# pathfinder_sch.net
KiCad netlist of a schematic drawn in Altium Designer
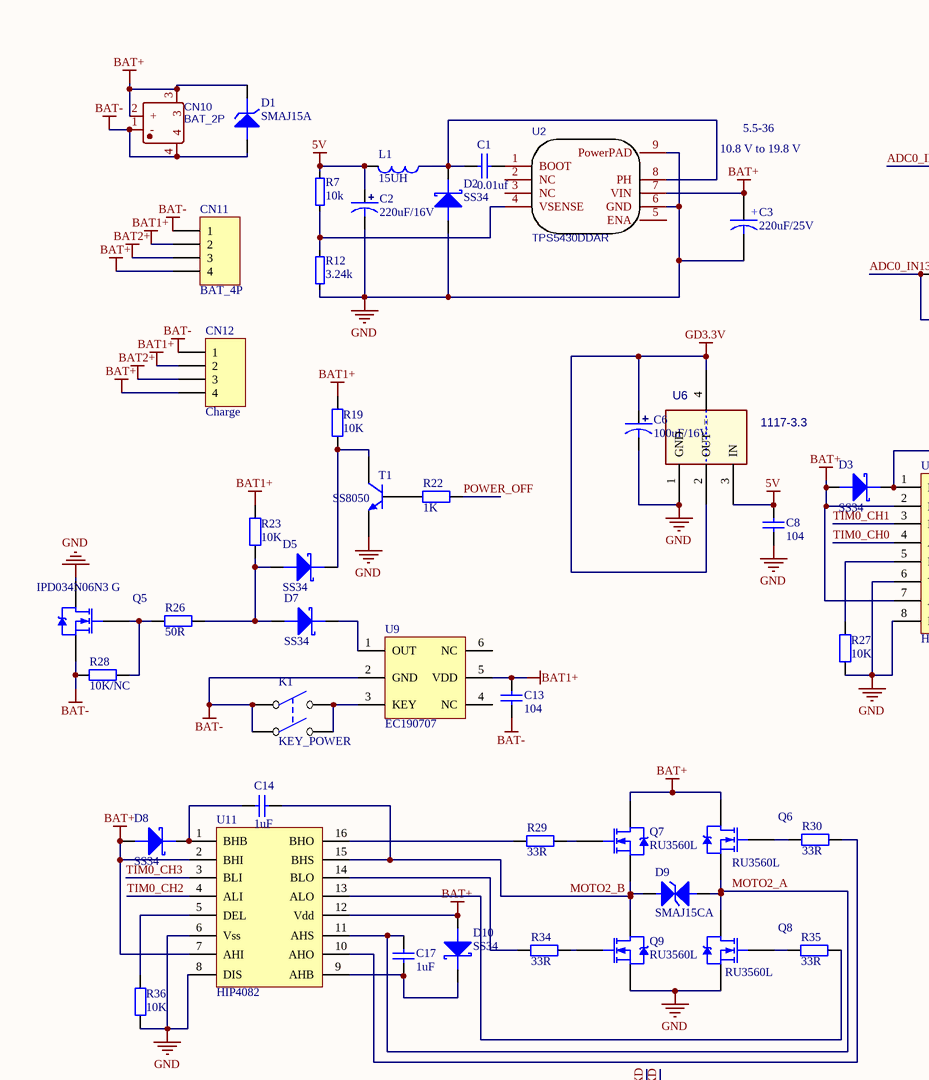
[diagram p0: pathfinder_sch.SchDoc, top left]
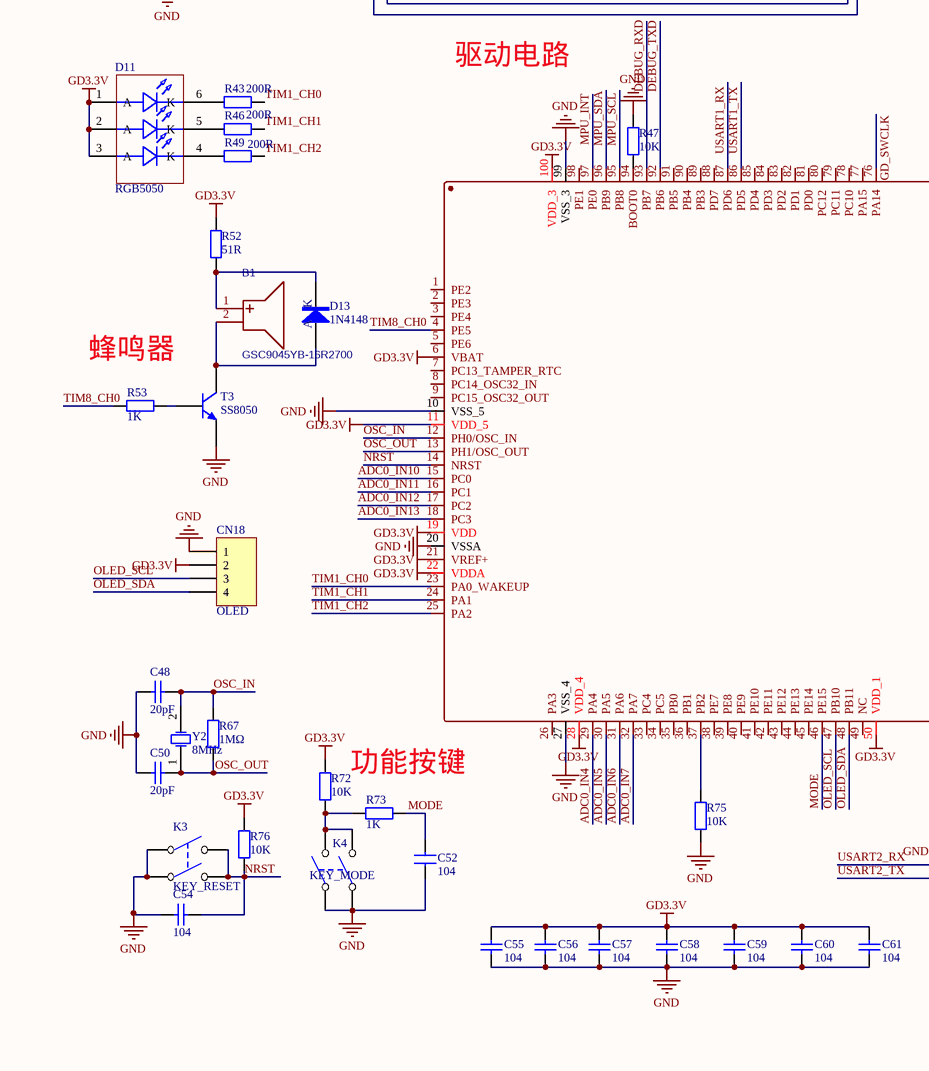
[diagram p1: pathfinder_sch.SchDoc, bottom left]
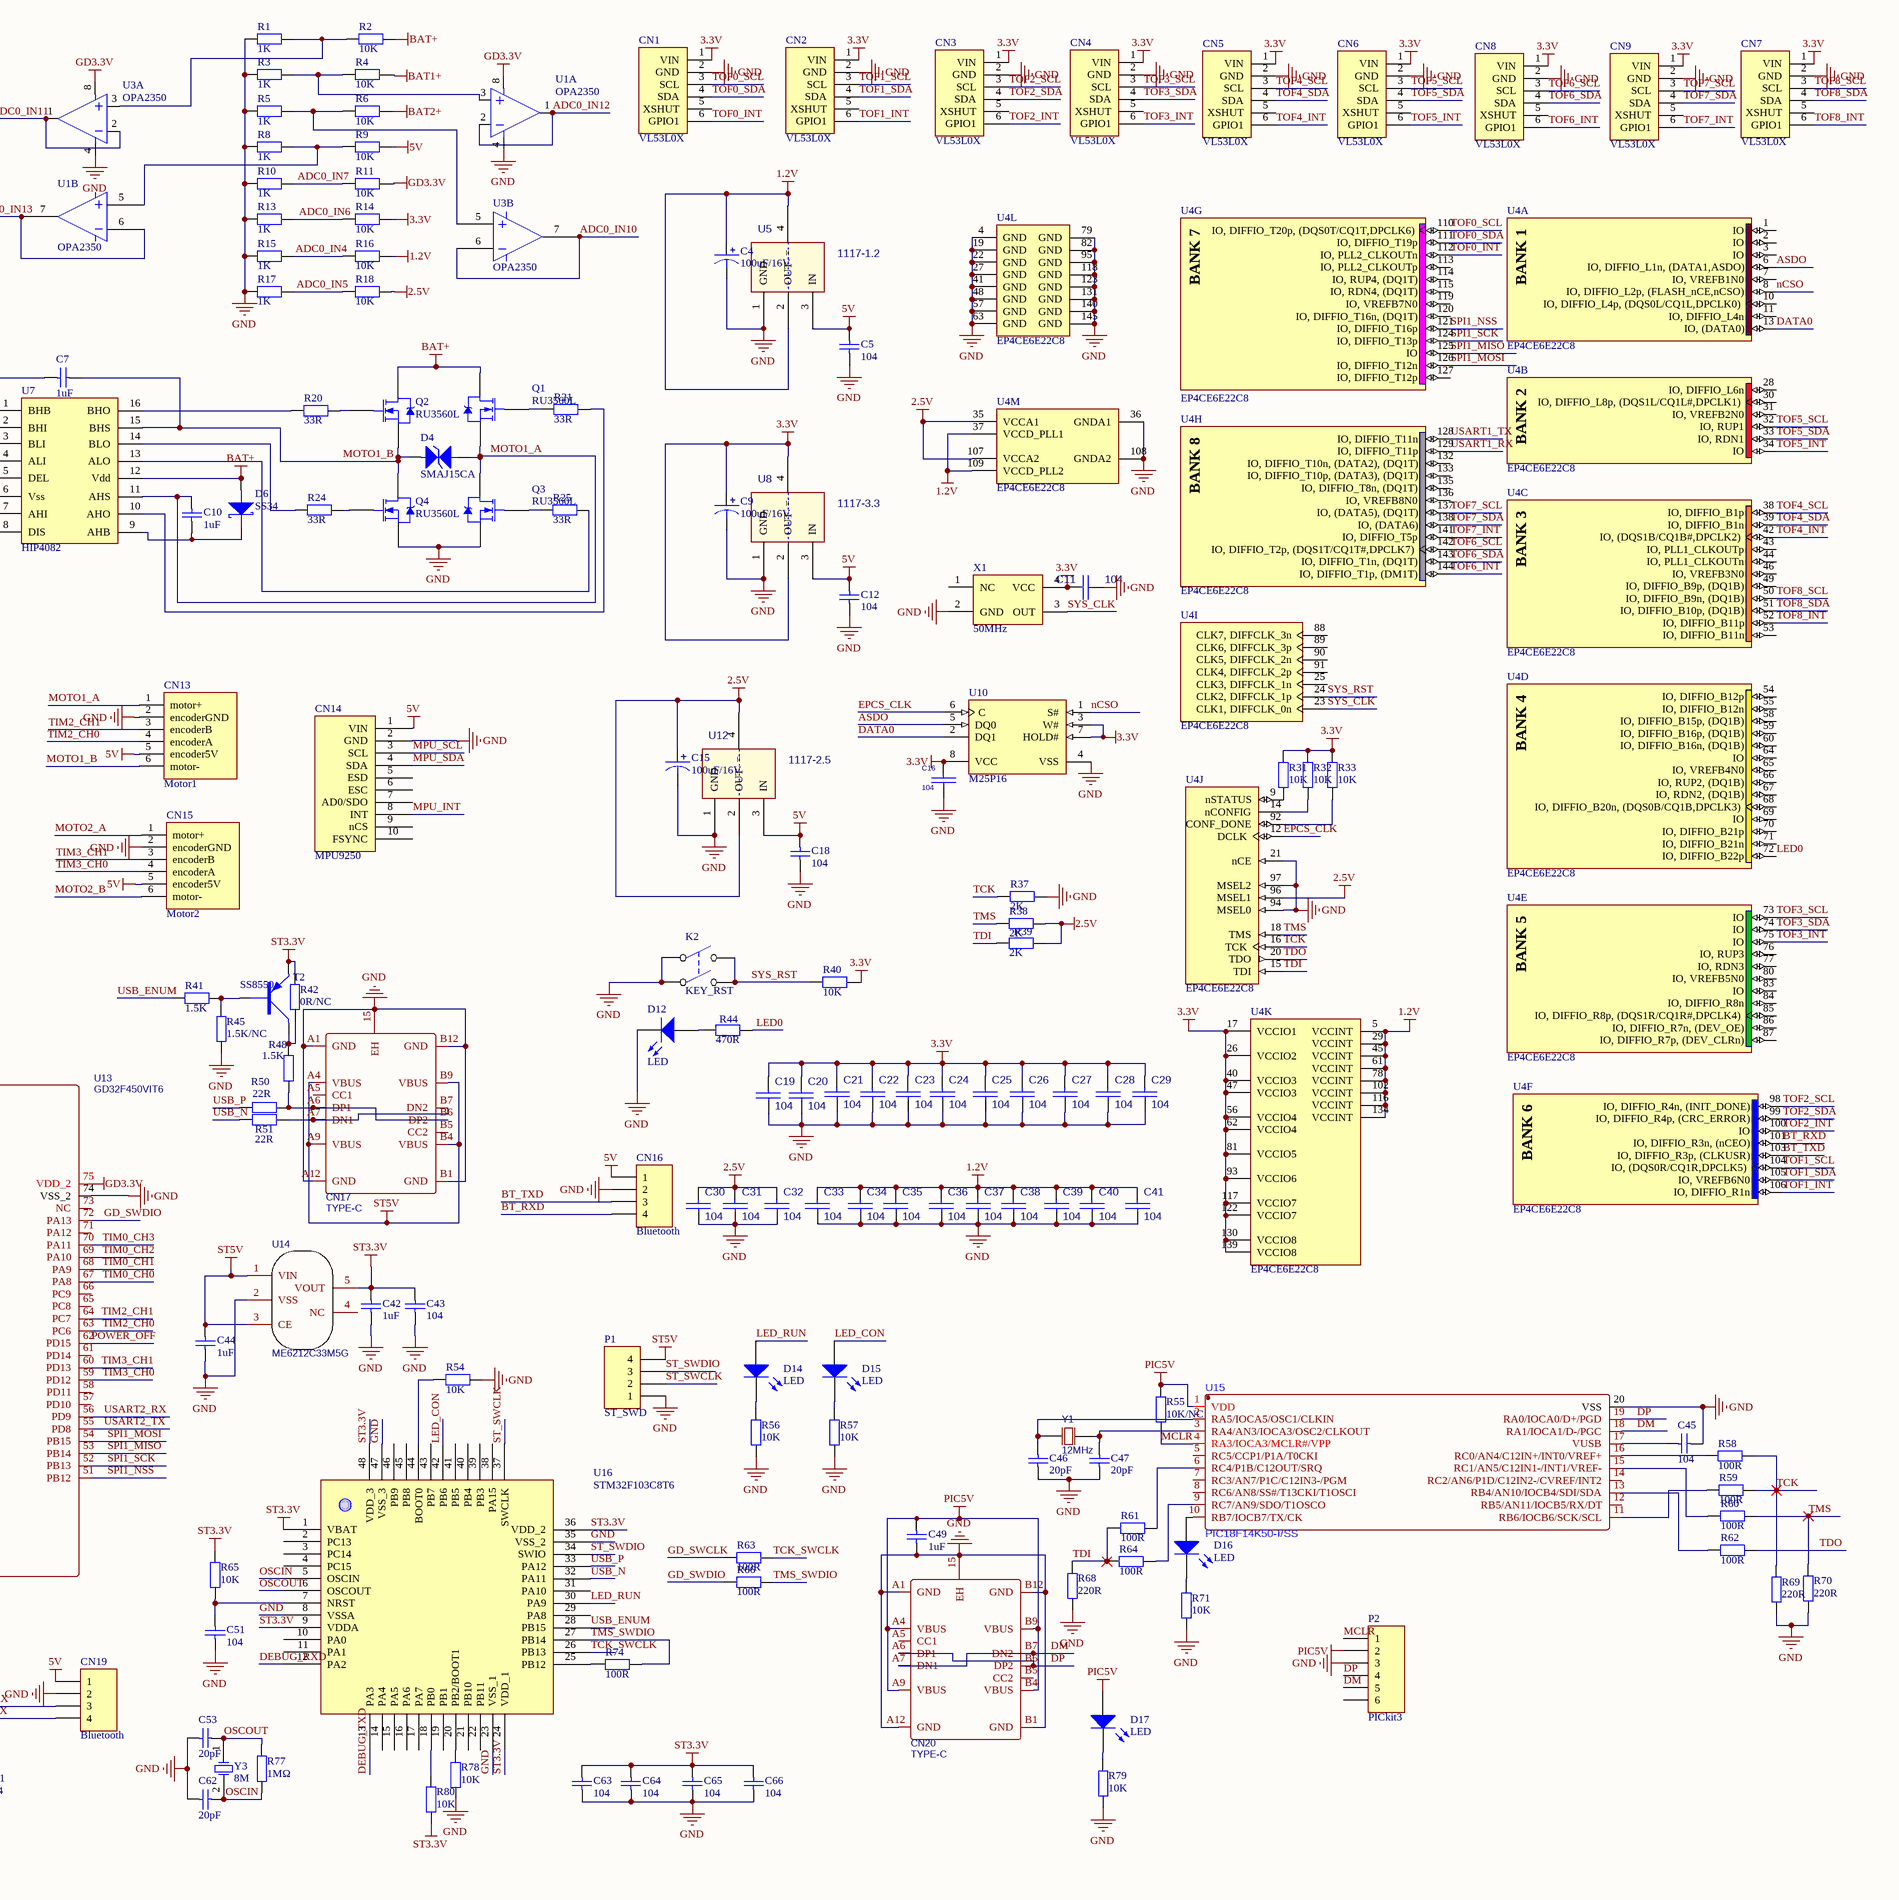
[diagram p2: pathfinder_sch.SchDoc, bottom right]

(export (version "E")
  (design (tool "Eeschema 10.0.6"))
  (components
    (comp (ref "B1")
      (value "GSC9045YB-16R2700")
      (footprint "BUZ-SMD_GSC9045YB-16R2700")
      (description "无源蜂鸣器")
      (fields (field (name "BOM_SUPPLIER PART") "C255324") (field (name "CONTRIBUTOR") "LCSC"))
      (libsource (lib "1") (part "GSC9045YB-16R2700"))
    )
    (comp (ref "C1")
      (value "0.01uf")
      (footprint "0603-JLC")
      (description "C0603")
      (libsource (lib "电容") (part "普通电容"))
    )
    (comp (ref "C2")
      (value "220uF/16V")
      (footprint "SMD,6.3x5.3mm")
      (description "6.3*5.3mm铝电解电容")
      (libsource (lib "电容") (part "SMD_ECAP"))
    )
    (comp (ref "C3")
      (value "220uF/25V")
      (footprint "SMD,6.3x5.8mm")
      (description "贴片铝电解电容SMD,6.3x5.8mm")
      (libsource (lib "*") (part "CAP极性"))
    )
    (comp (ref "C4")
      (value "100uF/16V")
      (footprint "SMD,6.3x5.3mm")
      (description "6.3*5.3mm铝电解电容")
      (libsource (lib "电容") (part "SMD_ECAP"))
    )
    (comp (ref "C5")
      (value "104")
      (footprint "0603-JLC")
      (description "C0603")
      (fields (field (name "PUBLISHER") "Altium Limited"))
      (libsource (lib "Miscellaneous Devices") (part "Cap"))
    )
    (comp (ref "C6")
      (value "100uF/16V")
      (footprint "SMD,6.3x5.3mm")
      (description "6.3*5.3mm铝电解电容")
      (libsource (lib "电容") (part "SMD_ECAP"))
    )
    (comp (ref "C7")
      (value "1uF")
      (footprint "0603-JLC")
      (description "C0603")
      (fields (field (name "PUBLISHER") "Altium Limited"))
      (libsource (lib "Miscellaneous Devices") (part "Cap"))
    )
    (comp (ref "C8")
      (value "104")
      (footprint "0603-JLC")
      (description "C0603")
      (fields (field (name "PUBLISHER") "Altium Limited"))
      (libsource (lib "Miscellaneous Devices") (part "Cap"))
    )
    (comp (ref "C9")
      (value "100uF/16V")
      (footprint "SMD,6.3x5.3mm")
      (description "6.3*5.3mm铝电解电容")
      (libsource (lib "电容") (part "SMD_ECAP"))
    )
    (comp (ref "C10")
      (value "1uF")
      (footprint "0603-JLC")
      (description "C0603")
      (fields (field (name "PUBLISHER") "Altium Limited"))
      (libsource (lib "Miscellaneous Devices") (part "Cap"))
    )
    (comp (ref "C11")
      (value "104")
      (footprint "0603-JLC")
      (description "C0603")
      (libsource (lib "Miscellaneous Devices") (part "C_Dup3"))
    )
    (comp (ref "C12")
      (value "104")
      (footprint "0603-JLC")
      (description "C0603")
      (fields (field (name "PUBLISHER") "Altium Limited"))
      (libsource (lib "Miscellaneous Devices") (part "Cap"))
    )
    (comp (ref "C13")
      (value "104")
      (footprint "0603-JLC")
      (description "C0603")
      (fields (field (name "PUBLISHER") "Altium Limited"))
      (libsource (lib "Miscellaneous Devices") (part "Cap"))
    )
    (comp (ref "C14")
      (value "1uF")
      (footprint "0603-JLC")
      (description "C0603")
      (fields (field (name "PUBLISHER") "Altium Limited"))
      (libsource (lib "Miscellaneous Devices") (part "Cap"))
    )
    (comp (ref "C15")
      (value "100uF/16V")
      (footprint "SMD,6.3x5.3mm")
      (description "6.3*5.3mm铝电解电容")
      (libsource (lib "电容") (part "SMD_ECAP"))
    )
    (comp (ref "C16")
      (value "104")
      (footprint "0603-JLC")
      (description "C0603")
      (libsource (lib "Miscellaneous Devices") (part "C"))
    )
    (comp (ref "C17")
      (value "1uF")
      (footprint "0603-JLC")
      (description "C0603")
      (fields (field (name "PUBLISHER") "Altium Limited"))
      (libsource (lib "Miscellaneous Devices") (part "Cap"))
    )
    (comp (ref "C18")
      (value "104")
      (footprint "0603-JLC")
      (description "C0603")
      (fields (field (name "PUBLISHER") "Altium Limited"))
      (libsource (lib "Miscellaneous Devices") (part "Cap"))
    )
    (comp (ref "C19")
      (value "104")
      (footprint "0603-JLC")
      (description "C0603")
      (libsource (lib "Miscellaneous Devices") (part "C_Dup4"))
    )
    (comp (ref "C20")
      (value "104")
      (footprint "0603-JLC")
      (description "C0603")
      (libsource (lib "Miscellaneous Devices") (part "C_Dup4"))
    )
    (comp (ref "C21")
      (value "104")
      (footprint "0603-JLC")
      (description "C0603")
      (libsource (lib "Miscellaneous Devices") (part "C_Dup4"))
    )
    (comp (ref "C22")
      (value "104")
      (footprint "0603-JLC")
      (description "C0603")
      (libsource (lib "Miscellaneous Devices") (part "C_Dup4"))
    )
    (comp (ref "C23")
      (value "104")
      (footprint "0603-JLC")
      (description "C0603")
      (libsource (lib "Miscellaneous Devices") (part "C_Dup4"))
    )
    (comp (ref "C24")
      (value "104")
      (footprint "0603-JLC")
      (description "C0603")
      (libsource (lib "Miscellaneous Devices") (part "C_Dup4"))
    )
    (comp (ref "C25")
      (value "104")
      (footprint "0603-JLC")
      (description "C0603")
      (libsource (lib "Miscellaneous Devices") (part "C_Dup4"))
    )
    (comp (ref "C26")
      (value "104")
      (footprint "0603-JLC")
      (description "C0603")
      (libsource (lib "Miscellaneous Devices") (part "C_Dup4"))
    )
    (comp (ref "C27")
      (value "104")
      (footprint "0603-JLC")
      (description "C0603")
      (libsource (lib "Miscellaneous Devices") (part "C_Dup4"))
    )
    (comp (ref "C28")
      (value "104")
      (footprint "0603-JLC")
      (description "C0603")
      (libsource (lib "Miscellaneous Devices") (part "C_Dup4"))
    )
    (comp (ref "C29")
      (value "104")
      (footprint "0603-JLC")
      (description "C0603")
      (libsource (lib "Miscellaneous Devices") (part "C_Dup4"))
    )
    (comp (ref "C30")
      (value "104")
      (footprint "0603-JLC")
      (description "C0603")
      (libsource (lib "Miscellaneous Devices") (part "C_Dup4"))
    )
    (comp (ref "C31")
      (value "104")
      (footprint "0603-JLC")
      (description "C0603")
      (libsource (lib "Miscellaneous Devices") (part "C_Dup4"))
    )
    (comp (ref "C32")
      (value "104")
      (footprint "0603-JLC")
      (description "C0603")
      (libsource (lib "Miscellaneous Devices") (part "C_Dup4"))
    )
    (comp (ref "C33")
      (value "104")
      (footprint "0603-JLC")
      (description "C0603")
      (libsource (lib "Miscellaneous Devices") (part "C_Dup4"))
    )
    (comp (ref "C34")
      (value "104")
      (footprint "0603-JLC")
      (description "C0603")
      (libsource (lib "Miscellaneous Devices") (part "C_Dup4"))
    )
    (comp (ref "C35")
      (value "104")
      (footprint "0603-JLC")
      (description "C0603")
      (libsource (lib "Miscellaneous Devices") (part "C_Dup4"))
    )
    (comp (ref "C36")
      (value "104")
      (footprint "0603-JLC")
      (description "C0603")
      (libsource (lib "Miscellaneous Devices") (part "C_Dup4"))
    )
    (comp (ref "C37")
      (value "104")
      (footprint "0603-JLC")
      (description "C0603")
      (libsource (lib "Miscellaneous Devices") (part "C_Dup4"))
    )
    (comp (ref "C38")
      (value "104")
      (footprint "0603-JLC")
      (description "C0603")
      (libsource (lib "Miscellaneous Devices") (part "C_Dup4"))
    )
    (comp (ref "C39")
      (value "104")
      (footprint "0603-JLC")
      (description "C0603")
      (libsource (lib "Miscellaneous Devices") (part "C_Dup4"))
    )
    (comp (ref "C40")
      (value "104")
      (footprint "0603-JLC")
      (description "C0603")
      (libsource (lib "Miscellaneous Devices") (part "C_Dup4"))
    )
    (comp (ref "C41")
      (value "104")
      (footprint "0603-JLC")
      (description "C0603")
      (libsource (lib "Miscellaneous Devices") (part "C_Dup4"))
    )
    (comp (ref "C42")
      (value "1uF")
      (footprint "0603-JLC")
      (description "C0603")
      (fields (field (name "PUBLISHER") "Altium Limited"))
      (libsource (lib "Miscellaneous Devices") (part "Cap"))
    )
    (comp (ref "C43")
      (value "104")
      (footprint "0603-JLC")
      (description "C0603")
      (fields (field (name "PUBLISHER") "Altium Limited"))
      (libsource (lib "Miscellaneous Devices") (part "Cap"))
    )
    (comp (ref "C44")
      (value "1uF")
      (footprint "0603-JLC")
      (description "C0603")
      (fields (field (name "PUBLISHER") "Altium Limited"))
      (libsource (lib "Miscellaneous Devices") (part "Cap"))
    )
    (comp (ref "C45")
      (value "104")
      (footprint "0603-JLC")
      (description "C0603")
      (fields (field (name "PUBLISHER") "Altium Limited"))
      (libsource (lib "Miscellaneous Devices") (part "Cap"))
    )
    (comp (ref "C46")
      (value "20pF")
      (footprint "0603-JLC")
      (description "C0603")
      (fields (field (name "PUBLISHER") "Altium Limited"))
      (libsource (lib "STM32F103C8T6") (part "Cap"))
    )
    (comp (ref "C47")
      (value "20pF")
      (footprint "0603-JLC")
      (description "C0603")
      (fields (field (name "PUBLISHER") "Altium Limited"))
      (libsource (lib "STM32F103C8T6") (part "Cap"))
    )
    (comp (ref "C48")
      (value "20pF")
      (footprint "0603-JLC")
      (description "C0603")
      (fields (field (name "PUBLISHER") "Altium Limited"))
      (libsource (lib "Miscellaneous Devices") (part "Cap"))
    )
    (comp (ref "C49")
      (value "1uF")
      (footprint "0603-JLC")
      (description "C0603")
      (fields (field (name "PUBLISHER") "Altium Limited"))
      (libsource (lib "Miscellaneous Devices") (part "Cap"))
    )
    (comp (ref "C50")
      (value "20pF")
      (footprint "0603-JLC")
      (description "C0603")
      (fields (field (name "PUBLISHER") "Altium Limited"))
      (libsource (lib "Miscellaneous Devices") (part "Cap"))
    )
    (comp (ref "C51")
      (value "104")
      (footprint "0603-JLC")
      (description "C0603")
      (fields (field (name "PUBLISHER") "Altium Limited"))
      (libsource (lib "Miscellaneous Devices") (part "Cap"))
    )
    (comp (ref "C52")
      (value "104")
      (footprint "0603-JLC")
      (description "C0603")
      (libsource (lib "*") (part "CAP"))
    )
    (comp (ref "C53")
      (value "20pF")
      (footprint "0603-JLC")
      (description "C0603")
      (fields (field (name "PUBLISHER") "Altium Limited"))
      (libsource (lib "STM32F103C8T6") (part "Cap"))
    )
    (comp (ref "C54")
      (value "104")
      (footprint "0603-JLC")
      (description "C0603")
      (fields (field (name "PUBLISHER") "Altium Limited"))
      (libsource (lib "Miscellaneous Devices") (part "Cap"))
    )
    (comp (ref "C55")
      (value "104")
      (footprint "0603-JLC")
      (description "C0603")
      (fields (field (name "PUBLISHER") "Altium Limited"))
      (libsource (lib "Miscellaneous Devices") (part "Cap"))
    )
    (comp (ref "C56")
      (value "104")
      (footprint "0603-JLC")
      (description "C0603")
      (fields (field (name "PUBLISHER") "Altium Limited"))
      (libsource (lib "Miscellaneous Devices") (part "Cap"))
    )
    (comp (ref "C57")
      (value "104")
      (footprint "0603-JLC")
      (description "C0603")
      (fields (field (name "PUBLISHER") "Altium Limited"))
      (libsource (lib "Miscellaneous Devices") (part "Cap"))
    )
    (comp (ref "C58")
      (value "104")
      (footprint "0603-JLC")
      (description "C0603")
      (fields (field (name "PUBLISHER") "Altium Limited"))
      (libsource (lib "Miscellaneous Devices") (part "Cap"))
    )
    (comp (ref "C59")
      (value "104")
      (footprint "0603-JLC")
      (description "C0603")
      (fields (field (name "PUBLISHER") "Altium Limited"))
      (libsource (lib "Miscellaneous Devices") (part "Cap"))
    )
    (comp (ref "C60")
      (value "104")
      (footprint "0603-JLC")
      (description "C0603")
      (fields (field (name "PUBLISHER") "Altium Limited"))
      (libsource (lib "Miscellaneous Devices") (part "Cap"))
    )
    (comp (ref "C61")
      (value "104")
      (footprint "0603-JLC")
      (description "C0603")
      (fields (field (name "PUBLISHER") "Altium Limited"))
      (libsource (lib "Miscellaneous Devices") (part "Cap"))
    )
    (comp (ref "C62")
      (value "20pF")
      (footprint "0603-JLC")
      (description "C0603")
      (fields (field (name "PUBLISHER") "Altium Limited"))
      (libsource (lib "STM32F103C8T6") (part "Cap"))
    )
    (comp (ref "C63")
      (value "104")
      (footprint "0603-JLC")
      (description "C0603")
      (fields (field (name "PUBLISHER") "Altium Limited"))
      (libsource (lib "Miscellaneous Devices") (part "Cap"))
    )
    (comp (ref "C64")
      (value "104")
      (footprint "0603-JLC")
      (description "C0603")
      (fields (field (name "PUBLISHER") "Altium Limited"))
      (libsource (lib "Miscellaneous Devices") (part "Cap"))
    )
    (comp (ref "C65")
      (value "104")
      (footprint "0603-JLC")
      (description "C0603")
      (fields (field (name "PUBLISHER") "Altium Limited"))
      (libsource (lib "Miscellaneous Devices") (part "Cap"))
    )
    (comp (ref "C66")
      (value "104")
      (footprint "0603-JLC")
      (description "C0603")
      (fields (field (name "PUBLISHER") "Altium Limited"))
      (libsource (lib "Miscellaneous Devices") (part "Cap"))
    )
    (comp (ref "CN1")
      (value "VL53L0X")
      (footprint "HDR1X6")
      (description "弯针单排母座2.54mm 6P")
      (libsource (lib "Schlib1") (part "VL53L0X"))
    )
    (comp (ref "CN2")
      (value "VL53L0X")
      (footprint "HDR1X6")
      (description "弯针单排母座2.54mm 6P")
      (libsource (lib "Schlib1") (part "VL53L0X"))
    )
    (comp (ref "CN3")
      (value "VL53L0X")
      (footprint "HDR1X6")
      (description "弯针单排母座2.54mm 6P")
      (libsource (lib "Schlib1") (part "VL53L0X"))
    )
    (comp (ref "CN4")
      (value "VL53L0X")
      (footprint "HDR1X6")
      (description "弯针单排母座2.54mm 6P")
      (libsource (lib "Schlib1") (part "VL53L0X"))
    )
    (comp (ref "CN5")
      (value "VL53L0X")
      (footprint "HDR1X6")
      (description "弯针单排母座2.54mm 6P")
      (libsource (lib "Schlib1") (part "VL53L0X"))
    )
    (comp (ref "CN6")
      (value "VL53L0X")
      (footprint "HDR1X6")
      (description "弯针单排母座2.54mm 6P")
      (libsource (lib "Schlib1") (part "VL53L0X"))
    )
    (comp (ref "CN7")
      (value "VL53L0X")
      (footprint "HDR1X6")
      (description "弯针单排母座2.54mm 6P")
      (libsource (lib "Schlib1") (part "VL53L0X"))
    )
    (comp (ref "CN8")
      (value "VL53L0X")
      (footprint "HDR1X6")
      (description "弯针单排母座2.54mm 6P")
      (libsource (lib "Schlib1") (part "VL53L0X"))
    )
    (comp (ref "CN9")
      (value "VL53L0X")
      (footprint "HDR1X6")
      (description "弯针单排母座2.54mm 6P")
      (libsource (lib "Schlib1") (part "VL53L0X"))
    )
    (comp (ref "CN10")
      (value "BAT_2P")
      (footprint "CONN-TH_XT60PW-M")
      (description "板插卧式 XT60PW-M")
      (fields
        (field (name "BOM_SUPPLIER PART") "C98732")
        (field (name "BOM_MANUFACTURER PART") "XT60PW-M")
        (field (name "CONTRIBUTOR") "LCSC")
      )
      (libsource (lib "6") (part "XT60PW-M"))
    )
    (comp (ref "CN11")
      (value "BAT_4P")
      (footprint "CONN-TH_4P-P2.54_X8821WR-06S-N2SN")
      (description "卧式XH2.54 4P")
      (fields (field (name "PUBLISHER") "Altium Limited"))
      (libsource (lib "Miscellaneous Connectors") (part "Header 4"))
    )
    (comp (ref "CN12")
      (value "Charge")
      (footprint "CONN-TH_4P-P2.54_X8821WR-06S-N2SN")
      (description "卧式XH2.54 4P")
      (fields (field (name "PUBLISHER") "Altium Limited"))
      (libsource (lib "Miscellaneous Connectors") (part "Header 4"))
    )
    (comp (ref "CN13")
      (value "Motor1")
      (footprint "CONN-TH_6P-P2.50_X8821WR-06S-N2SN")
      (description "卧式XH2.54 6P")
      (libsource (lib "Schlib1") (part "Motor"))
    )
    (comp (ref "CN14")
      (value "MPU9250")
      (footprint "HDR1X10")
      (description "直针单排母座 10P")
      (libsource (lib "Schlib1") (part "MPU6050"))
    )
    (comp (ref "CN15")
      (value "Motor2")
      (footprint "CONN-TH_6P-P2.50_X8821WR-06S-N2SN")
      (description "卧式XH2.54 6P")
      (libsource (lib "Schlib1") (part "Motor"))
    )
    (comp (ref "CN16")
      (value "Bluetooth")
      (footprint "HDR1X4")
      (description "直针单排母座 4P")
      (fields (field (name "PUBLISHER") "Altium Limited"))
      (libsource (lib "Miscellaneous Connectors") (part "Header 4"))
    )
    (comp (ref "CN17")
      (value "TYPE-C")
      (footprint "TYPE-C-SMD_918-468K2029Y50001")
      (description "立式Type-C母座14pin")
      (fields
        (field (name "BOM_SUPPLIER PART") "C709023")
        (field (name "BOM_MANUFACTURER PART") "918-468K2029Y50001")
        (field (name "CONTRIBUTOR") "LCSC")
      )
      (libsource (lib "Sheet_1_2022-03-06") (part "TYPE-C"))
    )
    (comp (ref "CN18")
      (value "OLED")
      (footprint "HDR1X4")
      (description "直针单排母座 4P")
      (fields (field (name "PUBLISHER") "Altium Limited"))
      (libsource (lib "Miscellaneous Connectors") (part "Header 4"))
    )
    (comp (ref "CN19")
      (value "Bluetooth")
      (footprint "HDR1X4")
      (description "直针单排母座 4P")
      (fields (field (name "PUBLISHER") "Altium Limited"))
      (libsource (lib "Miscellaneous Connectors") (part "Header 4"))
    )
    (comp (ref "CN20")
      (value "TYPE-C")
      (footprint "TYPE-C-SMD_918-468K2029Y50001")
      (description "立式Type-C母座14pin")
      (fields
        (field (name "BOM_SUPPLIER PART") "C709023")
        (field (name "BOM_MANUFACTURER PART") "918-468K2029Y50001")
        (field (name "CONTRIBUTOR") "LCSC")
      )
      (libsource (lib "Sheet_1_2022-03-06") (part "TYPE-C"))
    )
    (comp (ref "D1")
      (value "SMAJ15A")
      (footprint "SMA(DO-214AC)")
      (description "单向TVS管")
      (libsource (lib "Pathfinder_pcb") (part "DIODE ZENER"))
    )
    (comp (ref "D2")
      (value "SS34")
      (footprint "SMA(DO-214AC)")
      (description "肖特基二极管")
      (libsource (lib "二极管") (part "DIODE SCHOTTKY"))
    )
    (comp (ref "D3")
      (value "SS34")
      (footprint "SMA(DO-214AC)")
      (description "肖特基二极管")
      (libsource (lib "二极管") (part "DIODE SCHOTTKY"))
    )
    (comp (ref "D4")
      (value "SMAJ15CA")
      (footprint "SMA(DO-214AC)")
      (description "双向TVS管")
      (libsource (lib "Pathfinder_pcb") (part "TVS"))
    )
    (comp (ref "D5")
      (value "SS34")
      (footprint "SMA(DO-214AC)")
      (description "肖特基二极管")
      (libsource (lib "二极管") (part "DIODE SCHOTTKY"))
    )
    (comp (ref "D6")
      (value "SS34")
      (footprint "SMA(DO-214AC)")
      (description "肖特基二极管")
      (libsource (lib "二极管") (part "DIODE SCHOTTKY"))
    )
    (comp (ref "D7")
      (value "SS34")
      (footprint "SMA(DO-214AC)")
      (description "肖特基二极管")
      (libsource (lib "二极管") (part "DIODE SCHOTTKY"))
    )
    (comp (ref "D8")
      (value "SS34")
      (footprint "SMA(DO-214AC)")
      (description "肖特基二极管")
      (libsource (lib "二极管") (part "DIODE SCHOTTKY"))
    )
    (comp (ref "D9")
      (value "SMAJ15CA")
      (footprint "SMA(DO-214AC)")
      (description "双向TVS管")
      (libsource (lib "Pathfinder_pcb") (part "TVS"))
    )
    (comp (ref "D10")
      (value "SS34")
      (footprint "SMA(DO-214AC)")
      (description "肖特基二极管")
      (libsource (lib "二极管") (part "DIODE SCHOTTKY"))
    )
    (comp (ref "D11")
      (value "RGB5050")
      (footprint "LED-SMD_6P-L5.0-W5.0-FD")
      (description "5050灯珠")
      (libsource (lib "Pathfinder_pcb") (part "RGB5050"))
    )
    (comp (ref "D12")
      (value "LED")
      (footprint "0603LED")
      (description "0603白色LED")
      (fields (field (name "PUBLISHER") "Altium Limited"))
      (libsource (lib "running car pcb") (part "LED3"))
    )
    (comp (ref "D13")
      (value "1N4148")
      (footprint "1206")
      (description "Diode")
      (libsource (lib "*") (part "DIODE"))
    )
    (comp (ref "D14")
      (value "LED")
      (footprint "0603LED")
      (description "0603白色LED")
      (fields (field (name "PUBLISHER") "Altium Limited"))
      (libsource (lib "running car pcb") (part "LED3"))
    )
    (comp (ref "D15")
      (value "LED")
      (footprint "0603LED")
      (description "0603白色LED")
      (fields (field (name "PUBLISHER") "Altium Limited"))
      (libsource (lib "running car pcb") (part "LED3"))
    )
    (comp (ref "D16")
      (value "LED")
      (footprint "0603LED")
      (description "0603白色LED")
      (fields (field (name "PUBLISHER") "Altium Limited"))
      (libsource (lib "running car pcb") (part "LED3"))
    )
    (comp (ref "D17")
      (value "LED")
      (footprint "0603LED")
      (description "0603白色LED")
      (fields (field (name "PUBLISHER") "Altium Limited"))
      (libsource (lib "running car pcb") (part "LED3"))
    )
    (comp (ref "K1")
      (value "KEY_POWER")
      (footprint "SW-6/6")
      (description "贴片轻触开关")
      (libsource (lib "*") (part "SW DPST"))
    )
    (comp (ref "K2")
      (value "KEY_RST")
      (footprint "SW-6/6")
      (description "贴片轻触开关")
      (libsource (lib "*") (part "SW DPST"))
    )
    (comp (ref "K3")
      (value "KEY_RESET")
      (footprint "SW-6/6")
      (description "贴片轻触开关")
      (libsource (lib "*") (part "SW DPST"))
    )
    (comp (ref "K4")
      (value "KEY_MODE")
      (footprint "SW-6/6")
      (description "贴片轻触开关")
      (libsource (lib "*") (part "SW DPST"))
    )
    (comp (ref "L1")
      (value "15UH")
      (footprint "IND-SMD_L7.1-W6.6")
      (description "一体成型功率电感")
      (libsource (lib "常用元件库") (part "L"))
    )
    (comp (ref "P1")
      (value "ST_SWD")
      (footprint "HDR1X4")
      (description "Header, 4-Pin")
      (fields (field (name "PUBLISHER") "Altium Limited"))
      (libsource (lib "") (part "Header 4_1"))
    )
    (comp (ref "P2")
      (value "PICkit3")
      (footprint "HDR1X6")
      (description "Header, 6-Pin")
      (fields (field (name "PUBLISHER") "Altium Limited"))
      (libsource (lib "Miscellaneous Connectors") (part "Header 6"))
    )
    (comp (ref "Q1")
      (value "RU3560L")
      (footprint "TO-252-3L")
      (description "NMOSFET")
      (fields
        (field (name "MANUFACTURER") "International Rectifier")
        (field (name "PUBLISHER") "Altium Limited")
      )
      (libsource (lib "DMESC_1") (part "IRFR1205"))
    )
    (comp (ref "Q2")
      (value "RU3560L")
      (footprint "TO-252-3L")
      (description "NMOSFET")
      (fields
        (field (name "MANUFACTURER") "International Rectifier")
        (field (name "PUBLISHER") "Altium Limited")
      )
      (libsource (lib "DMESC_1") (part "IRFR1205"))
    )
    (comp (ref "Q3")
      (value "RU3560L")
      (footprint "TO-252-3L")
      (description "NMOSFET")
      (fields
        (field (name "MANUFACTURER") "International Rectifier")
        (field (name "PUBLISHER") "Altium Limited")
      )
      (libsource (lib "DMESC_1") (part "IRFR1205"))
    )
    (comp (ref "Q4")
      (value "RU3560L")
      (footprint "TO-252-3L")
      (description "NMOSFET")
      (fields
        (field (name "MANUFACTURER") "International Rectifier")
        (field (name "PUBLISHER") "Altium Limited")
      )
      (libsource (lib "DMESC_1") (part "IRFR1205"))
    )
    (comp (ref "Q5")
      (value "IPD034N06N3 G")
      (footprint "TO-252-3_L6.5-W5.8-P4.58-TL")
      (description "NMOSFET")
      (fields
        (field (name "MANUFACTURER") "International Rectifier")
        (field (name "PUBLISHER") "Altium Limited")
      )
      (libsource (lib "DMESC_1") (part "IRFR1205"))
    )
    (comp (ref "Q6")
      (value "RU3560L")
      (footprint "TO-252-3L")
      (description "NMOSFET")
      (fields
        (field (name "MANUFACTURER") "International Rectifier")
        (field (name "PUBLISHER") "Altium Limited")
      )
      (libsource (lib "DMESC_1") (part "IRFR1205"))
    )
    (comp (ref "Q7")
      (value "RU3560L")
      (footprint "TO-252-3L")
      (description "NMOSFET")
      (fields
        (field (name "MANUFACTURER") "International Rectifier")
        (field (name "PUBLISHER") "Altium Limited")
      )
      (libsource (lib "DMESC_1") (part "IRFR1205"))
    )
    (comp (ref "Q8")
      (value "RU3560L")
      (footprint "TO-252-3L")
      (description "NMOSFET")
      (fields
        (field (name "MANUFACTURER") "International Rectifier")
        (field (name "PUBLISHER") "Altium Limited")
      )
      (libsource (lib "DMESC_1") (part "IRFR1205"))
    )
    (comp (ref "Q9")
      (value "RU3560L")
      (footprint "TO-252-3L")
      (description "NMOSFET")
      (fields
        (field (name "MANUFACTURER") "International Rectifier")
        (field (name "PUBLISHER") "Altium Limited")
      )
      (libsource (lib "DMESC_1") (part "IRFR1205"))
    )
    (comp (ref "R1")
      (value "1K")
      (footprint "0603-JLC")
      (description "R0603")
      (fields (field (name "PUBLISHER") "Altium Limited"))
      (libsource (lib "") (part "Res2_1"))
    )
    (comp (ref "R2")
      (value "10K")
      (footprint "0603-JLC")
      (description "R0603")
      (fields (field (name "PUBLISHER") "Altium Limited"))
      (libsource (lib "") (part "Res2_1"))
    )
    (comp (ref "R3")
      (value "1K")
      (footprint "0603-JLC")
      (description "R0603")
      (fields (field (name "PUBLISHER") "Altium Limited"))
      (libsource (lib "") (part "Res2_1"))
    )
    (comp (ref "R4")
      (value "10K")
      (footprint "0603-JLC")
      (description "R0603")
      (fields (field (name "PUBLISHER") "Altium Limited"))
      (libsource (lib "") (part "Res2_1"))
    )
    (comp (ref "R5")
      (value "1K")
      (footprint "0603-JLC")
      (description "R0603")
      (fields (field (name "PUBLISHER") "Altium Limited"))
      (libsource (lib "") (part "Res2_1"))
    )
    (comp (ref "R6")
      (value "10K")
      (footprint "0603-JLC")
      (description "R0603")
      (fields (field (name "PUBLISHER") "Altium Limited"))
      (libsource (lib "") (part "Res2_1"))
    )
    (comp (ref "R7")
      (value "10k")
      (footprint "0603-JLC")
      (description "R0603")
      (libsource (lib "电阻") (part "RES"))
    )
    (comp (ref "R8")
      (value "1K")
      (footprint "0603-JLC")
      (description "R0603")
      (fields (field (name "PUBLISHER") "Altium Limited"))
      (libsource (lib "") (part "Res2_1"))
    )
    (comp (ref "R9")
      (value "10K")
      (footprint "0603-JLC")
      (description "R0603")
      (fields (field (name "PUBLISHER") "Altium Limited"))
      (libsource (lib "") (part "Res2_1"))
    )
    (comp (ref "R10")
      (value "1K")
      (footprint "0603-JLC")
      (description "R0603")
      (fields (field (name "PUBLISHER") "Altium Limited"))
      (libsource (lib "") (part "Res2_1"))
    )
    (comp (ref "R11")
      (value "10K")
      (footprint "0603-JLC")
      (description "R0603")
      (fields (field (name "PUBLISHER") "Altium Limited"))
      (libsource (lib "") (part "Res2_1"))
    )
    (comp (ref "R12")
      (value "3.24k")
      (footprint "0603-JLC")
      (description "R0603")
      (libsource (lib "电阻") (part "RES"))
    )
    (comp (ref "R13")
      (value "1K")
      (footprint "0603-JLC")
      (description "R0603")
      (fields (field (name "PUBLISHER") "Altium Limited"))
      (libsource (lib "") (part "Res2_1"))
    )
    (comp (ref "R14")
      (value "10K")
      (footprint "0603-JLC")
      (description "R0603")
      (fields (field (name "PUBLISHER") "Altium Limited"))
      (libsource (lib "") (part "Res2_1"))
    )
    (comp (ref "R15")
      (value "1K")
      (footprint "0603-JLC")
      (description "R0603")
      (fields (field (name "PUBLISHER") "Altium Limited"))
      (libsource (lib "") (part "Res2_1"))
    )
    (comp (ref "R16")
      (value "10K")
      (footprint "0603-JLC")
      (description "R0603")
      (fields (field (name "PUBLISHER") "Altium Limited"))
      (libsource (lib "") (part "Res2_1"))
    )
    (comp (ref "R17")
      (value "1K")
      (footprint "0603-JLC")
      (description "R0603")
      (fields (field (name "PUBLISHER") "Altium Limited"))
      (libsource (lib "") (part "Res2_1"))
    )
    (comp (ref "R18")
      (value "10K")
      (footprint "0603-JLC")
      (description "R0603")
      (fields (field (name "PUBLISHER") "Altium Limited"))
      (libsource (lib "") (part "Res2_1"))
    )
    (comp (ref "R19")
      (value "10K")
      (footprint "0603-JLC")
      (description "R0603")
      (fields (field (name "PUBLISHER") "Altium Limited"))
      (libsource (lib "") (part "Res2_3"))
    )
    (comp (ref "R20")
      (value "33R")
      (footprint "0603-JLC")
      (description "R0603")
      (fields (field (name "PUBLISHER") "Altium Limited"))
      (libsource (lib "") (part "Res2_2"))
    )
    (comp (ref "R21")
      (value "33R")
      (footprint "0603-JLC")
      (description "R0603")
      (fields (field (name "PUBLISHER") "Altium Limited"))
      (libsource (lib "") (part "Res2_2"))
    )
    (comp (ref "R22")
      (value "1K")
      (footprint "0603-JLC")
      (description "R0603")
      (fields (field (name "PUBLISHER") "Altium Limited"))
      (libsource (lib "") (part "Res2_2"))
    )
    (comp (ref "R23")
      (value "10K")
      (footprint "0603-JLC")
      (description "R0603")
      (fields (field (name "PUBLISHER") "Altium Limited"))
      (libsource (lib "Miscellaneous Devices") (part "Res2"))
    )
    (comp (ref "R24")
      (value "33R")
      (footprint "0603-JLC")
      (description "R0603")
      (fields (field (name "PUBLISHER") "Altium Limited"))
      (libsource (lib "") (part "Res2_2"))
    )
    (comp (ref "R25")
      (value "33R")
      (footprint "0603-JLC")
      (description "R0603")
      (fields (field (name "PUBLISHER") "Altium Limited"))
      (libsource (lib "") (part "Res2_2"))
    )
    (comp (ref "R26")
      (value "50R")
      (footprint "0603-JLC")
      (description "R0603")
      (fields (field (name "PUBLISHER") "Altium Limited"))
      (libsource (lib "") (part "Res2_2"))
    )
    (comp (ref "R27")
      (value "10K")
      (footprint "0603-JLC")
      (description "R0603")
      (fields (field (name "PUBLISHER") "Altium Limited"))
      (libsource (lib "Miscellaneous Devices") (part "Res2"))
    )
    (comp (ref "R28")
      (value "10K/NC")
      (footprint "0603-JLC")
      (description "R0603")
      (fields (field (name "PUBLISHER") "Altium Limited"))
      (libsource (lib "") (part "Res2_2"))
    )
    (comp (ref "R29")
      (value "33R")
      (footprint "0603-JLC")
      (description "R0603")
      (fields (field (name "PUBLISHER") "Altium Limited"))
      (libsource (lib "") (part "Res2_2"))
    )
    (comp (ref "R30")
      (value "33R")
      (footprint "0603-JLC")
      (description "R0603")
      (fields (field (name "PUBLISHER") "Altium Limited"))
      (libsource (lib "") (part "Res2_2"))
    )
    (comp (ref "R31")
      (value "10K")
      (footprint "0603-JLC")
      (description "R0603")
      (fields (field (name "PUBLISHER") "Altium Limited"))
      (libsource (lib "") (part "Res2_2"))
    )
    (comp (ref "R32")
      (value "10K")
      (footprint "0603-JLC")
      (description "R0603")
      (fields (field (name "PUBLISHER") "Altium Limited"))
      (libsource (lib "") (part "Res2_2"))
    )
    (comp (ref "R33")
      (value "10K")
      (footprint "0603-JLC")
      (description "R0603")
      (fields (field (name "PUBLISHER") "Altium Limited"))
      (libsource (lib "") (part "Res2_2"))
    )
    (comp (ref "R34")
      (value "33R")
      (footprint "0603-JLC")
      (description "R0603")
      (fields (field (name "PUBLISHER") "Altium Limited"))
      (libsource (lib "") (part "Res2_2"))
    )
    (comp (ref "R35")
      (value "33R")
      (footprint "0603-JLC")
      (description "R0603")
      (fields (field (name "PUBLISHER") "Altium Limited"))
      (libsource (lib "") (part "Res2_2"))
    )
    (comp (ref "R36")
      (value "10K")
      (footprint "0603-JLC")
      (description "R0603")
      (fields (field (name "PUBLISHER") "Altium Limited"))
      (libsource (lib "Miscellaneous Devices") (part "Res2"))
    )
    (comp (ref "R37")
      (value "2K")
      (footprint "0603-JLC")
      (description "R0603")
      (fields (field (name "PUBLISHER") "Altium Limited"))
      (libsource (lib "") (part "Res2_1"))
    )
    (comp (ref "R38")
      (value "2K")
      (footprint "0603-JLC")
      (description "R0603")
      (fields (field (name "PUBLISHER") "Altium Limited"))
      (libsource (lib "") (part "Res2_1"))
    )
    (comp (ref "R39")
      (value "2K")
      (footprint "0603-JLC")
      (description "R0603")
      (fields (field (name "PUBLISHER") "Altium Limited"))
      (libsource (lib "") (part "Res2_1"))
    )
    (comp (ref "R40")
      (value "10K")
      (footprint "0603-JLC")
      (description "R0603")
      (fields (field (name "PUBLISHER") "Altium Limited"))
      (libsource (lib "") (part "Res2_1"))
    )
    (comp (ref "R41")
      (value "1.5K")
      (footprint "0603-JLC")
      (description "R0603")
      (fields (field (name "PUBLISHER") "Altium Limited"))
      (libsource (lib "") (part "Res2_1"))
    )
    (comp (ref "R42")
      (value "0R/NC")
      (footprint "0603-JLC")
      (description "R0603")
      (fields (field (name "PUBLISHER") "Altium Limited"))
      (libsource (lib "") (part "Res2_3"))
    )
    (comp (ref "R43")
      (value "200R")
      (footprint "0603-JLC")
      (description "R0603")
      (fields (field (name "PUBLISHER") "Altium Limited"))
      (libsource (lib "") (part "Res2_2"))
    )
    (comp (ref "R44")
      (value "470R")
      (footprint "0603-JLC")
      (description "R0603")
      (fields (field (name "PUBLISHER") "Altium Limited"))
      (libsource (lib "") (part "Res2_1"))
    )
    (comp (ref "R45")
      (value "1.5K/NC")
      (footprint "0603-JLC")
      (description "R0603")
      (fields (field (name "PUBLISHER") "Altium Limited"))
      (libsource (lib "") (part "Res2_3"))
    )
    (comp (ref "R46")
      (value "200R")
      (footprint "0603-JLC")
      (description "R0603")
      (fields (field (name "PUBLISHER") "Altium Limited"))
      (libsource (lib "") (part "Res2_2"))
    )
    (comp (ref "R47")
      (value "10K")
      (footprint "0603-JLC")
      (description "R0603")
      (fields (field (name "PUBLISHER") "Altium Limited"))
      (libsource (lib "") (part "Res2_3"))
    )
    (comp (ref "R48")
      (value "1.5K")
      (footprint "0603-JLC")
      (description "R0603")
      (fields (field (name "PUBLISHER") "Altium Limited"))
      (libsource (lib "") (part "Res2_3"))
    )
    (comp (ref "R49")
      (value "200R")
      (footprint "0603-JLC")
      (description "R0603")
      (fields (field (name "PUBLISHER") "Altium Limited"))
      (libsource (lib "") (part "Res2_2"))
    )
    (comp (ref "R50")
      (value "22R")
      (footprint "0603-JLC")
      (description "R0603")
      (fields (field (name "PUBLISHER") "Altium Limited"))
      (libsource (lib "") (part "Res2_1"))
    )
    (comp (ref "R51")
      (value "22R")
      (footprint "0603-JLC")
      (description "R0603")
      (fields (field (name "PUBLISHER") "Altium Limited"))
      (libsource (lib "") (part "Res2_1"))
    )
    (comp (ref "R52")
      (value "51R")
      (footprint "0603-JLC")
      (description "R0603")
      (fields (field (name "PUBLISHER") "Altium Limited"))
      (libsource (lib "") (part "Res2_3"))
    )
    (comp (ref "R53")
      (value "1K")
      (footprint "0603-JLC")
      (description "R0603")
      (fields (field (name "PUBLISHER") "Altium Limited"))
      (libsource (lib "") (part "Res2_1"))
    )
    (comp (ref "R54")
      (value "10K")
      (footprint "0603-JLC")
      (description "R0603")
      (fields (field (name "PUBLISHER") "Altium Limited"))
      (libsource (lib "STM32F103C8T6") (part "Res2"))
    )
    (comp (ref "R55")
      (value "10K/NC")
      (footprint "0603-JLC")
      (description "R0603")
      (fields (field (name "PUBLISHER") "Altium Limited"))
      (libsource (lib "") (part "Res2_2"))
    )
    (comp (ref "R56")
      (value "10K")
      (footprint "0603-JLC")
      (description "R0603")
      (fields (field (name "PUBLISHER") "Altium Limited"))
      (libsource (lib "") (part "Res2_2"))
    )
    (comp (ref "R57")
      (value "10K")
      (footprint "0603-JLC")
      (description "R0603")
      (fields (field (name "PUBLISHER") "Altium Limited"))
      (libsource (lib "") (part "Res2_2"))
    )
    (comp (ref "R58")
      (value "100R")
      (footprint "0603-JLC")
      (description "R0603")
      (fields (field (name "PUBLISHER") "Altium Limited"))
      (libsource (lib "") (part "Res2_1"))
    )
    (comp (ref "R59")
      (value "100R")
      (footprint "0603-JLC")
      (description "R0603")
      (fields (field (name "PUBLISHER") "Altium Limited"))
      (libsource (lib "") (part "Res2_1"))
    )
    (comp (ref "R60")
      (value "100R")
      (footprint "0603-JLC")
      (description "R0603")
      (fields (field (name "PUBLISHER") "Altium Limited"))
      (libsource (lib "") (part "Res2_1"))
    )
    (comp (ref "R61")
      (value "100R")
      (footprint "0603-JLC")
      (description "R0603")
      (fields (field (name "PUBLISHER") "Altium Limited"))
      (libsource (lib "") (part "Res2_1"))
    )
    (comp (ref "R62")
      (value "100R")
      (footprint "0603-JLC")
      (description "R0603")
      (fields (field (name "PUBLISHER") "Altium Limited"))
      (libsource (lib "") (part "Res2_1"))
    )
    (comp (ref "R63")
      (value "100R")
      (footprint "0603-JLC")
      (description "R0603")
      (fields (field (name "PUBLISHER") "Altium Limited"))
      (libsource (lib "STM32F103C8T6") (part "Res2"))
    )
    (comp (ref "R64")
      (value "100R")
      (footprint "0603-JLC")
      (description "R0603")
      (fields (field (name "PUBLISHER") "Altium Limited"))
      (libsource (lib "") (part "Res2_1"))
    )
    (comp (ref "R65")
      (value "10K")
      (footprint "0603-JLC")
      (description "R0603")
      (fields (field (name "PUBLISHER") "Altium Limited"))
      (libsource (lib "") (part "Res2_2"))
    )
    (comp (ref "R66")
      (value "100R")
      (footprint "0603-JLC")
      (description "R0603")
      (fields (field (name "PUBLISHER") "Altium Limited"))
      (libsource (lib "STM32F103C8T6") (part "Res2"))
    )
    (comp (ref "R67")
      (value "1MΩ")
      (footprint "0603-JLC")
      (description "R0603")
      (fields (field (name "PUBLISHER") "Altium Limited"))
      (libsource (lib "Miscellaneous Devices") (part "Res2"))
    )
    (comp (ref "R68")
      (value "220R")
      (footprint "0603-JLC")
      (description "R0603")
      (fields (field (name "PUBLISHER") "Altium Limited"))
      (libsource (lib "") (part "Res2_2"))
    )
    (comp (ref "R69")
      (value "220R")
      (footprint "0603-JLC")
      (description "R0603")
      (fields (field (name "PUBLISHER") "Altium Limited"))
      (libsource (lib "") (part "Res2_2"))
    )
    (comp (ref "R70")
      (value "220R")
      (footprint "0603-JLC")
      (description "R0603")
      (fields (field (name "PUBLISHER") "Altium Limited"))
      (libsource (lib "") (part "Res2_2"))
    )
    (comp (ref "R71")
      (value "10K")
      (footprint "0603-JLC")
      (description "R0603")
      (fields (field (name "PUBLISHER") "Altium Limited"))
      (libsource (lib "") (part "Res2_2"))
    )
    (comp (ref "R72")
      (value "10K")
      (footprint "0603-JLC")
      (description "R0603")
      (fields (field (name "PUBLISHER") "Altium Limited"))
      (libsource (lib "Miscellaneous Devices") (part "Res2"))
    )
    (comp (ref "R73")
      (value "1K")
      (footprint "0603-JLC")
      (description "R0603")
      (fields (field (name "PUBLISHER") "Altium Limited"))
      (libsource (lib "") (part "Res2_2"))
    )
    (comp (ref "R74")
      (value "100R")
      (footprint "0603-JLC")
      (description "R0603")
      (fields (field (name "PUBLISHER") "Altium Limited"))
      (libsource (lib "STM32F103C8T6") (part "Res2"))
    )
    (comp (ref "R75")
      (value "10K")
      (footprint "0603-JLC")
      (description "R0603")
      (fields (field (name "PUBLISHER") "Altium Limited"))
      (libsource (lib "") (part "Res2_3"))
    )
    (comp (ref "R76")
      (value "10K")
      (footprint "0603-JLC")
      (description "R0603")
      (fields (field (name "PUBLISHER") "Altium Limited"))
      (libsource (lib "Miscellaneous Devices") (part "Res2"))
    )
    (comp (ref "R77")
      (value "1MΩ")
      (footprint "0603-JLC")
      (description "R0603")
      (fields (field (name "PUBLISHER") "Altium Limited"))
      (libsource (lib "") (part "Res2_2"))
    )
    (comp (ref "R78")
      (value "10K")
      (footprint "0603-JLC")
      (description "R0603")
      (fields (field (name "PUBLISHER") "Altium Limited"))
      (libsource (lib "") (part "Res2_2"))
    )
    (comp (ref "R79")
      (value "10K")
      (footprint "0603-JLC")
      (description "R0603")
      (fields (field (name "PUBLISHER") "Altium Limited"))
      (libsource (lib "") (part "Res2_2"))
    )
    (comp (ref "R80")
      (value "10K")
      (footprint "0603-JLC")
      (description "R0603")
      (fields (field (name "PUBLISHER") "Altium Limited"))
      (libsource (lib "") (part "Res2_2"))
    )
    (comp (ref "T1")
      (value "SS8050")
      (footprint "SOT-23")
      (description "NPN三极管")
      (libsource (lib "DMESC_1") (part "2N3904"))
    )
    (comp (ref "T2")
      (value "SS8550")
      (footprint "SOT-23")
      (description "PNP三极管")
      (libsource (lib "三极管") (part "PNP"))
    )
    (comp (ref "T3")
      (value "SS8050")
      (footprint "SOT-23")
      (description "NPN三极管")
      (libsource (lib "DMESC_1") (part "2N3904"))
    )
    (comp (ref "U1")
      (value "OPA2350")
      (footprint "SOP_8")
      (description "两路运放芯片")
      (libsource (lib "necktest") (part "OPA2350"))
    )
    (comp (ref "U2")
      (value "TPS5430DDAR")
      (footprint "SOIC-8_L5.0-W4.0-P1.27-LS6.0-BL-EP2.0")
      (description "DCDC降压芯片")
      (fields (field (name "BOM_SUPPLIER PART") "C9864"))
      (libsource (lib "2") (part "TPS5430DDAR"))
    )
    (comp (ref "U3")
      (value "OPA2350")
      (footprint "SOP_8")
      (description "两路运放芯片")
      (libsource (lib "necktest") (part "OPA2350"))
    )
    (comp (ref "U4")
      (value "EP4CE6E22C8")
      (footprint "EQFP144_L")
      (description "FPGA")
      (fields (field (name "PUBLISHER") "Altium Limited"))
      (libsource (lib "necktest_2") (part "EP4CE6E22C8"))
    )
    (comp (ref "U5")
      (value "1117-1.2")
      (footprint "SOT223")
      (description "线性稳压1.2V")
      (libsource (lib "altium-import") (part "root_0_1117-3.3_"))
    )
    (comp (ref "U6")
      (value "1117-3.3")
      (footprint "SOT223")
      (description "线性稳压3.3V")
      (libsource (lib "altium-import") (part "root_0_1117-3.3_"))
    )
    (comp (ref "U7")
      (value "HIP4082")
      (footprint "HIP4082b")
      (description "H桥驱动芯片")
      (libsource (lib "lr7843_new") (part "HIP4082"))
    )
    (comp (ref "U8")
      (value "1117-3.3")
      (footprint "SOT223")
      (description "线性稳压3.3V")
      (libsource (lib "altium-import") (part "root_0_1117-3.3_"))
    )
    (comp (ref "U9")
      (value "EC190707")
      (footprint "SOT-23-6_L2.9-W1.6-P0.95-LS2.8-BL")
      (description "电子开关芯片")
      (libsource (lib "Schlib1") (part "EC190707"))
    )
    (comp (ref "U10")
      (value "M25P16")
      (footprint "SOIC-8_150mil")
      (description "FLASH存储芯片")
      (fields (field (name "VOLTAGE") "2.7V-3.6V爘ISHIDDEN=T") (field (name "MANUFACTURER") "Micron"))
      (libsource (lib "altium-import") (part "root_0_M25P16-VMN3PB_"))
    )
    (comp (ref "U11")
      (value "HIP4082")
      (footprint "HIP4082b")
      (description "H桥驱动芯片")
      (libsource (lib "lr7843_new") (part "HIP4082"))
    )
    (comp (ref "U12")
      (value "1117-2.5")
      (footprint "SOT223")
      (description "线性稳压2.5V")
      (libsource (lib "altium-import") (part "root_0_1117-3.3_"))
    )
    (comp (ref "U13")
      (value "GD32F450VIT6")
      (footprint "LQFP-100_L14.0-W14.0-P0.50-LS16.0-BL")
      (description "单片机")
      (fields (field (name "BOM_SUPPLIER PART") "C98441"))
      (libsource (lib "Sheet_1_2022-03-03") (part "GD32F450VIT6"))
    )
    (comp (ref "U14")
      (value "ME6212C33M5G")
      (footprint "ME6212C33M5G")
      (description "线性稳压3.3V")
      (fields (field (name "BOM_SUPPLIER PART") "C81233"))
      (libsource (lib "Sheet_1_2021-08-16") (part "ME6212C33M5G"))
    )
    (comp (ref "U15")
      (value "PIC18F14K50-I/SS")
      (footprint "SSOP-20_L7.2-W5.3-P0.65-LS7.8-BL")
      (description "单片机")
      (libsource (lib "2") (part "PIC18F14K50-I/SS"))
    )
    (comp (ref "U16")
      (value "STM32F103C8T6")
      (footprint "STM32F103C6T6")
      (description "单片机")
      (libsource (lib "STM32F103C8T6") (part "STM32F103C8T6"))
    )
    (comp (ref "X1")
      (value "50MHz")
      (footprint "SMD-7050_4P")
      (description "贴片有源晶振")
      (libsource (lib "Schlib1") (part "50MHZ有源晶振"))
    )
    (comp (ref "Y1")
      (value "12MHz")
      (footprint "HC-49S_L11.4-W4.8")
      (description "贴片无源晶振")
      (fields
        (field (name "BOM_SUPPLIER PART") "C188206")
        (field (name "BOM_MANUFACTURER PART") "X49SM12MSB2SI")
        (field (name "CONTRIBUTOR") "LCSC")
      )
      (libsource (lib "3") (part "12MHz"))
    )
    (comp (ref "Y2")
      (value "8MHz")
      (footprint "3225")
      (description "贴片无源晶振")
      (fields (field (name "PUBLISHER") "Altium Limited"))
      (libsource (lib "Miscellaneous Devices") (part "XTAL"))
    )
    (comp (ref "Y3")
      (value "8M")
      (footprint "3225")
      (description "贴片无源晶振")
      (fields (field (name "PUBLISHER") "Altium Limited"))
      (libsource (lib "STM32F103C8T6") (part "XTAL"))
    )
  )
  (nets
    (net (code "1") (name "/ADC0_IN4") (class "Default")
      (node (ref "R15") (pin "2") (pinfunction "2_2") (pintype "passive"))
      (node (ref "R16") (pin "1") (pinfunction "1_1") (pintype "passive"))
      (node (ref "U13") (pin "29") (pinfunction "PA4_29") (pintype "passive"))
    )
    (net (code "2") (name "/ADC0_IN5") (class "Default")
      (node (ref "R17") (pin "2") (pinfunction "2_2") (pintype "passive"))
      (node (ref "R18") (pin "1") (pinfunction "1_1") (pintype "passive"))
      (node (ref "U13") (pin "30") (pinfunction "PA5_30") (pintype "passive"))
    )
    (net (code "3") (name "/ADC0_IN6") (class "Default")
      (node (ref "R13") (pin "2") (pinfunction "2_2") (pintype "passive"))
      (node (ref "R14") (pin "1") (pinfunction "1_1") (pintype "passive"))
      (node (ref "U13") (pin "31") (pinfunction "PA6_31") (pintype "passive"))
    )
    (net (code "4") (name "/ADC0_IN7") (class "Default")
      (node (ref "R10") (pin "2") (pinfunction "2_2") (pintype "passive"))
      (node (ref "R11") (pin "1") (pinfunction "1_1") (pintype "passive"))
      (node (ref "U13") (pin "32") (pinfunction "PA7_32") (pintype "passive"))
    )
    (net (code "5") (name "/ADC0_IN10") (class "Default")
      (node (ref "U13") (pin "15") (pinfunction "PC0_15") (pintype "passive"))
      (node (ref "U3") (pin "6") (pintype "passive"))
      (node (ref "U3") (pin "7") (pintype "passive"))
    )
    (net (code "6") (name "/ADC0_IN11") (class "Default")
      (node (ref "U13") (pin "16") (pinfunction "PC1_16") (pintype "passive"))
      (node (ref "U3") (pin "1") (pintype "passive"))
      (node (ref "U3") (pin "2") (pintype "passive"))
    )
    (net (code "7") (name "/ADC0_IN12") (class "Default")
      (node (ref "U1") (pin "1") (pintype "passive"))
      (node (ref "U1") (pin "2") (pintype "passive"))
      (node (ref "U13") (pin "17") (pinfunction "PC2_17") (pintype "passive"))
    )
    (net (code "8") (name "/ADC0_IN13") (class "Default")
      (node (ref "U1") (pin "6") (pintype "passive"))
      (node (ref "U1") (pin "7") (pintype "passive"))
      (node (ref "U13") (pin "18") (pinfunction "PC3_18") (pintype "passive"))
    )
    (net (code "9") (name "/ASDO") (class "Default")
      (node (ref "U10") (pin "5") (pinfunction "DQ0_5") (pintype "input"))
      (node (ref "U4") (pin "6") (pinfunction "IO,_DIFFIO_L1n,_(DATA1,ASDO)_6") (pintype "bidirectional"))
    )
    (net (code "10") (name "/BT_RXD") (class "Default")
      (node (ref "CN16") (pin "4") (pinfunction "4_4") (pintype "passive"))
      (node (ref "U4") (pin "101") (pinfunction "IO,_DIFFIO_R3n,_(nCEO)_101") (pintype "bidirectional"))
    )
    (net (code "11") (name "/BT_TXD") (class "Default")
      (node (ref "CN16") (pin "3") (pinfunction "3_3") (pintype "passive"))
      (node (ref "U4") (pin "103") (pinfunction "IO,_DIFFIO_R3p,_(CLKUSR)_103") (pintype "bidirectional"))
    )
    (net (code "12") (name "/DATA0") (class "Default")
      (node (ref "U10") (pin "2") (pinfunction "DQ1_2") (pintype "tri_state"))
      (node (ref "U4") (pin "13") (pinfunction "IO,_(DATA0)_13") (pintype "bidirectional"))
    )
    (net (code "13") (name "/DEBUG_RXD") (class "Default")
      (node (ref "U13") (pin "93") (pinfunction "PB7_93") (pintype "passive"))
      (node (ref "U16") (pin "12") (pinfunction "PA2_12") (pintype "passive"))
    )
    (net (code "14") (name "/DEBUG_TXD") (class "Default")
      (node (ref "U13") (pin "92") (pinfunction "PB6_92") (pintype "passive"))
      (node (ref "U16") (pin "13") (pinfunction "PA3_13") (pintype "passive"))
    )
    (net (code "15") (name "/DM") (class "Default")
      (node (ref "CN20") (pin "A7") (pinfunction "DN1_A7") (pintype "passive"))
      (node (ref "CN20") (pin "B7") (pinfunction "DN2_B7") (pintype "passive"))
      (node (ref "P2") (pin "5") (pinfunction "5_5") (pintype "passive"))
      (node (ref "U15") (pin "18") (pinfunction "RA1/IOCA1/D-/PGC_18") (pintype "passive"))
    )
    (net (code "16") (name "/DP") (class "Default")
      (node (ref "CN20") (pin "A6") (pinfunction "DP1_A6") (pintype "passive"))
      (node (ref "CN20") (pin "B6") (pinfunction "DP2_B6") (pintype "passive"))
      (node (ref "P2") (pin "4") (pinfunction "4_4") (pintype "passive"))
      (node (ref "U15") (pin "19") (pinfunction "RA0/IOCA0/D+/PGD_19") (pintype "passive"))
    )
    (net (code "17") (name "/EPCS_CLK") (class "Default")
      (node (ref "U10") (pin "6") (pinfunction "C_6") (pintype "input"))
      (node (ref "U4") (pin "12") (pinfunction "DCLK_12") (pintype "bidirectional"))
    )
    (net (code "18") (name "/GD_SWCLK") (class "Default")
      (node (ref "R63") (pin "1") (pinfunction "1_1") (pintype "passive"))
      (node (ref "U13") (pin "76") (pinfunction "PA14_76") (pintype "passive"))
    )
    (net (code "19") (name "/GD_SWDIO") (class "Default")
      (node (ref "R66") (pin "1") (pinfunction "1_1") (pintype "passive"))
      (node (ref "U13") (pin "72") (pinfunction "PA13_72") (pintype "passive"))
    )
    (net (code "20") (name "/LED0") (class "Default")
      (node (ref "R44") (pin "1") (pinfunction "1_1") (pintype "passive"))
      (node (ref "U4") (pin "72") (pinfunction "IO,_DIFFIO_B22p_72") (pintype "bidirectional"))
    )
    (net (code "21") (name "/LED_CON") (class "Default")
      (node (ref "D15") (pin "1") (pinfunction "A_1") (pintype "passive"))
      (node (ref "U16") (pin "42") (pinfunction "PB6_42") (pintype "passive"))
    )
    (net (code "22") (name "/LED_RUN") (class "Default")
      (node (ref "D14") (pin "1") (pinfunction "A_1") (pintype "passive"))
      (node (ref "U16") (pin "30") (pinfunction "PA9_30") (pintype "passive"))
    )
    (net (code "23") (name "/MCLR") (class "Default")
      (node (ref "P2") (pin "1") (pinfunction "1_1") (pintype "passive"))
      (node (ref "R55") (pin "1") (pinfunction "1_1") (pintype "passive"))
      (node (ref "U15") (pin "4") (pinfunction "RA3/IOCA3/MCLR#/VPP_4") (pintype "passive"))
    )
    (net (code "24") (name "/MODE") (class "Default")
      (node (ref "C52") (pin "1") (pinfunction "1_1") (pintype "passive"))
      (node (ref "R73") (pin "1") (pinfunction "1_1") (pintype "passive"))
      (node (ref "U13") (pin "46") (pinfunction "PE15_46") (pintype "passive"))
    )
    (net (code "25") (name "/MOTO1_A") (class "Default")
      (node (ref "C10") (pin "2") (pinfunction "2_2") (pintype "passive"))
      (node (ref "CN13") (pin "1") (pinfunction "motor+_1") (pintype "passive"))
      (node (ref "D4") (pin "2") (pinfunction "K_2") (pintype "passive"))
      (node (ref "Q1") (pin "3") (pinfunction "S_3") (pintype "passive"))
      (node (ref "Q3") (pin "2") (pinfunction "D_2") (pintype "passive"))
      (node (ref "U7") (pin "11") (pinfunction "AHS_11") (pintype "passive"))
    )
    (net (code "26") (name "/MOTO1_B") (class "Default")
      (node (ref "C7") (pin "2") (pinfunction "2_2") (pintype "passive"))
      (node (ref "CN13") (pin "6") (pinfunction "motor-_6") (pintype "passive"))
      (node (ref "D4") (pin "1") (pinfunction "A_1") (pintype "passive"))
      (node (ref "Q2") (pin "3") (pinfunction "S_3") (pintype "passive"))
      (node (ref "Q4") (pin "2") (pinfunction "D_2") (pintype "passive"))
      (node (ref "U7") (pin "15") (pinfunction "BHS_15") (pintype "passive"))
    )
    (net (code "27") (name "/MOTO2_A") (class "Default")
      (node (ref "C17") (pin "2") (pinfunction "2_2") (pintype "passive"))
      (node (ref "CN15") (pin "1") (pinfunction "motor+_1") (pintype "passive"))
      (node (ref "D9") (pin "2") (pinfunction "K_2") (pintype "passive"))
      (node (ref "Q6") (pin "3") (pinfunction "S_3") (pintype "passive"))
      (node (ref "Q8") (pin "2") (pinfunction "D_2") (pintype "passive"))
      (node (ref "U11") (pin "11") (pinfunction "AHS_11") (pintype "passive"))
    )
    (net (code "28") (name "/MOTO2_B") (class "Default")
      (node (ref "C14") (pin "2") (pinfunction "2_2") (pintype "passive"))
      (node (ref "CN15") (pin "6") (pinfunction "motor-_6") (pintype "passive"))
      (node (ref "D9") (pin "1") (pinfunction "A_1") (pintype "passive"))
      (node (ref "Q7") (pin "3") (pinfunction "S_3") (pintype "passive"))
      (node (ref "Q9") (pin "2") (pinfunction "D_2") (pintype "passive"))
      (node (ref "U11") (pin "15") (pinfunction "BHS_15") (pintype "passive"))
    )
    (net (code "29") (name "/MPU_INT") (class "Default")
      (node (ref "CN14") (pin "8") (pinfunction "INT_8") (pintype "passive"))
      (node (ref "U13") (pin "97") (pinfunction "PE0_97") (pintype "passive"))
    )
    (net (code "30") (name "/MPU_SCL") (class "Default")
      (node (ref "CN14") (pin "3") (pinfunction "SCL_3") (pintype "passive"))
      (node (ref "U13") (pin "95") (pinfunction "PB8_95") (pintype "passive"))
    )
    (net (code "31") (name "/MPU_SDA") (class "Default")
      (node (ref "CN14") (pin "4") (pinfunction "SDA_4") (pintype "passive"))
      (node (ref "U13") (pin "96") (pinfunction "PB9_96") (pintype "passive"))
    )
    (net (code "32") (name "/NRST") (class "Default")
      (node (ref "C54") (pin "2") (pinfunction "2_2") (pintype "passive"))
      (node (ref "K3") (pin "2") (pinfunction "NO1_2") (pintype "passive"))
      (node (ref "R76") (pin "1") (pinfunction "1_1") (pintype "passive"))
      (node (ref "U13") (pin "14") (pinfunction "NRST_14") (pintype "passive"))
    )
    (net (code "33") (name "/OLED_SCL") (class "Default")
      (node (ref "CN18") (pin "3") (pinfunction "3_3") (pintype "passive"))
      (node (ref "U13") (pin "47") (pinfunction "PB10_47") (pintype "passive"))
    )
    (net (code "34") (name "/OLED_SDA") (class "Default")
      (node (ref "CN18") (pin "4") (pinfunction "4_4") (pintype "passive"))
      (node (ref "U13") (pin "48") (pinfunction "PB11_48") (pintype "passive"))
    )
    (net (code "35") (name "/OSCIN") (class "Default")
      (node (ref "C62") (pin "2") (pinfunction "2_2") (pintype "passive"))
      (node (ref "R77") (pin "1") (pinfunction "1_1") (pintype "passive"))
      (node (ref "U16") (pin "5") (pinfunction "OSCIN_5") (pintype "passive"))
      (node (ref "Y3") (pin "2") (pinfunction "2_2") (pintype "passive"))
    )
    (net (code "36") (name "/OSCOUT") (class "Default")
      (node (ref "C53") (pin "2") (pinfunction "2_2") (pintype "passive"))
      (node (ref "R77") (pin "2") (pinfunction "2_2") (pintype "passive"))
      (node (ref "U16") (pin "6") (pinfunction "OSCOUT_6") (pintype "passive"))
      (node (ref "Y3") (pin "1") (pinfunction "1_1") (pintype "passive"))
    )
    (net (code "37") (name "/OSC_IN") (class "Default")
      (node (ref "C48") (pin "2") (pinfunction "2_2") (pintype "passive"))
      (node (ref "R67") (pin "2") (pinfunction "2_2") (pintype "passive"))
      (node (ref "U13") (pin "12") (pinfunction "PH0/OSC_IN_12") (pintype "passive"))
      (node (ref "Y2") (pin "2") (pinfunction "OSC2_2") (pintype "passive"))
    )
    (net (code "38") (name "/OSC_OUT") (class "Default")
      (node (ref "C50") (pin "2") (pinfunction "2_2") (pintype "passive"))
      (node (ref "R67") (pin "1") (pinfunction "1_1") (pintype "passive"))
      (node (ref "U13") (pin "13") (pinfunction "PH1/OSC_OUT_13") (pintype "passive"))
      (node (ref "Y2") (pin "1") (pinfunction "OSC1_1") (pintype "passive"))
    )
    (net (code "39") (name "/POWER_OFF") (class "Default")
      (node (ref "R22") (pin "1") (pinfunction "1_1") (pintype "passive"))
      (node (ref "U13") (pin "62") (pinfunction "PD15_62") (pintype "passive"))
    )
    (net (code "40") (name "/SPI1_MISO") (class "Default")
      (node (ref "U13") (pin "53") (pinfunction "PB14_53") (pintype "passive"))
      (node (ref "U4") (pin "125") (pinfunction "IO_125") (pintype "bidirectional"))
    )
    (net (code "41") (name "/SPI1_MOSI") (class "Default")
      (node (ref "U13") (pin "54") (pinfunction "PB15_54") (pintype "passive"))
      (node (ref "U4") (pin "126") (pinfunction "IO,_DIFFIO_T12n_126") (pintype "bidirectional"))
    )
    (net (code "42") (name "/SPI1_NSS") (class "Default")
      (node (ref "U13") (pin "51") (pinfunction "PB12_51") (pintype "passive"))
      (node (ref "U4") (pin "121") (pinfunction "IO,_DIFFIO_T16p_121") (pintype "bidirectional"))
    )
    (net (code "43") (name "/SPI1_SCK") (class "Default")
      (node (ref "U13") (pin "52") (pinfunction "PB13_52") (pintype "passive"))
      (node (ref "U4") (pin "124") (pinfunction "IO,_DIFFIO_T13p_124") (pintype "bidirectional"))
    )
    (net (code "44") (name "/ST_SWCLK") (class "Default")
      (node (ref "P1") (pin "2") (pinfunction "2_2") (pintype "passive"))
      (node (ref "U16") (pin "37") (pinfunction "SWCLK_37") (pintype "passive"))
    )
    (net (code "45") (name "/ST_SWDIO") (class "Default")
      (node (ref "P1") (pin "3") (pinfunction "3_3") (pintype "passive"))
      (node (ref "U16") (pin "34") (pinfunction "SWIO_34") (pintype "passive"))
    )
    (net (code "46") (name "/SYS_CLK") (class "Default")
      (node (ref "U4") (pin "23") (pinfunction "CLK1,_DIFFCLK_0n_23") (pintype "passive"))
      (node (ref "X1") (pin "3") (pinfunction "OUT_3") (pintype "passive"))
    )
    (net (code "47") (name "/SYS_RST") (class "Default")
      (node (ref "K2") (pin "2") (pinfunction "NO1_2") (pintype "passive"))
      (node (ref "R40") (pin "2") (pinfunction "2_2") (pintype "passive"))
      (node (ref "U4") (pin "24") (pinfunction "CLK2,_DIFFCLK_1p_24") (pintype "passive"))
    )
    (net (code "48") (name "/TCK") (class "Default")
      (node (ref "R37") (pin "2") (pinfunction "2_2") (pintype "passive"))
      (node (ref "R58") (pin "1") (pinfunction "1_1") (pintype "passive"))
      (node (ref "R59") (pin "1") (pinfunction "1_1") (pintype "passive"))
      (node (ref "R69") (pin "2") (pinfunction "2_2") (pintype "passive"))
      (node (ref "U4") (pin "16") (pinfunction "TCK_16") (pintype "input"))
    )
    (net (code "49") (name "/TCK_SWCLK") (class "Default")
      (node (ref "R63") (pin "2") (pinfunction "2_2") (pintype "passive"))
      (node (ref "U16") (pin "26") (pinfunction "PB13_26") (pintype "passive"))
    )
    (net (code "50") (name "/TDI") (class "Default")
      (node (ref "R39") (pin "2") (pinfunction "2_2") (pintype "passive"))
      (node (ref "R61") (pin "2") (pinfunction "2_2") (pintype "passive"))
      (node (ref "R64") (pin "2") (pinfunction "2_2") (pintype "passive"))
      (node (ref "R68") (pin "2") (pinfunction "2_2") (pintype "passive"))
      (node (ref "U4") (pin "15") (pinfunction "TDI_15") (pintype "input"))
    )
    (net (code "51") (name "/TDO") (class "Default")
      (node (ref "R62") (pin "1") (pinfunction "1_1") (pintype "passive"))
      (node (ref "U4") (pin "20") (pinfunction "TDO_20") (pintype "output"))
    )
    (net (code "52") (name "/TIM0_CH0") (class "Default")
      (node (ref "U13") (pin "67") (pinfunction "PA8_67") (pintype "passive"))
      (node (ref "U7") (pin "4") (pinfunction "ALI_4") (pintype "passive"))
    )
    (net (code "53") (name "/TIM0_CH1") (class "Default")
      (node (ref "U13") (pin "68") (pinfunction "PA9_68") (pintype "passive"))
      (node (ref "U7") (pin "3") (pinfunction "BLI_3") (pintype "passive"))
    )
    (net (code "54") (name "/TIM0_CH2") (class "Default")
      (node (ref "U11") (pin "4") (pinfunction "ALI_4") (pintype "passive"))
      (node (ref "U13") (pin "69") (pinfunction "PA10_69") (pintype "passive"))
    )
    (net (code "55") (name "/TIM0_CH3") (class "Default")
      (node (ref "U11") (pin "3") (pinfunction "BLI_3") (pintype "passive"))
      (node (ref "U13") (pin "70") (pinfunction "PA11_70") (pintype "passive"))
    )
    (net (code "56") (name "/TIM1_CH0") (class "Default")
      (node (ref "R43") (pin "1") (pinfunction "1_1") (pintype "passive"))
      (node (ref "U13") (pin "23") (pinfunction "PA0_WAKEUP_23") (pintype "passive"))
    )
    (net (code "57") (name "/TIM1_CH1") (class "Default")
      (node (ref "R46") (pin "1") (pinfunction "1_1") (pintype "passive"))
      (node (ref "U13") (pin "24") (pinfunction "PA1_24") (pintype "passive"))
    )
    (net (code "58") (name "/TIM1_CH2") (class "Default")
      (node (ref "R49") (pin "1") (pinfunction "1_1") (pintype "passive"))
      (node (ref "U13") (pin "25") (pinfunction "PA2_25") (pintype "passive"))
    )
    (net (code "59") (name "/TIM2_CH0") (class "Default")
      (node (ref "CN13") (pin "4") (pinfunction "encoderA_4") (pintype "passive"))
      (node (ref "U13") (pin "63") (pinfunction "PC6_63") (pintype "passive"))
    )
    (net (code "60") (name "/TIM2_CH1") (class "Default")
      (node (ref "CN13") (pin "3") (pinfunction "encoderB_3") (pintype "passive"))
      (node (ref "U13") (pin "64") (pinfunction "PC7_64") (pintype "passive"))
    )
    (net (code "61") (name "/TIM3_CH0") (class "Default")
      (node (ref "CN15") (pin "4") (pinfunction "encoderA_4") (pintype "passive"))
      (node (ref "U13") (pin "59") (pinfunction "PD12_59") (pintype "passive"))
    )
    (net (code "62") (name "/TIM3_CH1") (class "Default")
      (node (ref "CN15") (pin "3") (pinfunction "encoderB_3") (pintype "passive"))
      (node (ref "U13") (pin "60") (pinfunction "PD13_60") (pintype "passive"))
    )
    (net (code "63") (name "/TIM8_CH0") (class "Default")
      (node (ref "R53") (pin "1") (pinfunction "1_1") (pintype "passive"))
      (node (ref "U13") (pin "4") (pinfunction "PE5_4") (pintype "passive"))
    )
    (net (code "64") (name "/TMS") (class "Default")
      (node (ref "R38") (pin "2") (pinfunction "2_2") (pintype "passive"))
      (node (ref "R60") (pin "1") (pinfunction "1_1") (pintype "passive"))
      (node (ref "R70") (pin "2") (pinfunction "2_2") (pintype "passive"))
      (node (ref "U4") (pin "18") (pinfunction "TMS_18") (pintype "input"))
    )
    (net (code "65") (name "/TMS_SWDIO") (class "Default")
      (node (ref "R66") (pin "2") (pinfunction "2_2") (pintype "passive"))
      (node (ref "R74") (pin "2") (pinfunction "2_2") (pintype "passive"))
      (node (ref "U16") (pin "27") (pinfunction "PB14_27") (pintype "passive"))
    )
    (net (code "66") (name "/TOF0_INT") (class "Default")
      (node (ref "CN1") (pin "6") (pinfunction "GPIO1_6") (pintype "passive"))
      (node (ref "U4") (pin "112") (pinfunction "IO,_PLL2_CLKOUTn_112") (pintype "bidirectional"))
    )
    (net (code "67") (name "/TOF0_SCL") (class "Default")
      (node (ref "CN1") (pin "3") (pinfunction "SCL_3") (pintype "passive"))
      (node (ref "U4") (pin "110") (pinfunction "IO,_DIFFIO_T20p,_(DQS0T/CQ1T,DPCLK6)_110") (pintype "bidirectional"))
    )
    (net (code "68") (name "/TOF0_SDA") (class "Default")
      (node (ref "CN1") (pin "4") (pinfunction "SDA_4") (pintype "passive"))
      (node (ref "U4") (pin "111") (pinfunction "IO,_DIFFIO_T19p_111") (pintype "bidirectional"))
    )
    (net (code "69") (name "/TOF1_INT") (class "Default")
      (node (ref "CN2") (pin "6") (pinfunction "GPIO1_6") (pintype "passive"))
      (node (ref "U4") (pin "106") (pinfunction "IO,_DIFFIO_R1n_106") (pintype "bidirectional"))
    )
    (net (code "70") (name "/TOF1_SCL") (class "Default")
      (node (ref "CN2") (pin "3") (pinfunction "SCL_3") (pintype "passive"))
      (node (ref "U4") (pin "104") (pinfunction "IO,_(DQS0R/CQ1R,DPCLK5)_104") (pintype "bidirectional"))
    )
    (net (code "71") (name "/TOF1_SDA") (class "Default")
      (node (ref "CN2") (pin "4") (pinfunction "SDA_4") (pintype "passive"))
      (node (ref "U4") (pin "105") (pinfunction "IO,_VREFB6N0_105") (pintype "bidirectional"))
    )
    (net (code "72") (name "/TOF2_INT") (class "Default")
      (node (ref "CN3") (pin "6") (pinfunction "GPIO1_6") (pintype "passive"))
      (node (ref "U4") (pin "100") (pinfunction "IO_100") (pintype "bidirectional"))
    )
    (net (code "73") (name "/TOF2_SCL") (class "Default")
      (node (ref "CN3") (pin "3") (pinfunction "SCL_3") (pintype "passive"))
      (node (ref "U4") (pin "98") (pinfunction "IO,_DIFFIO_R4n,_(INIT_DONE)_98") (pintype "bidirectional"))
    )
    (net (code "74") (name "/TOF2_SDA") (class "Default")
      (node (ref "CN3") (pin "4") (pinfunction "SDA_4") (pintype "passive"))
      (node (ref "U4") (pin "99") (pinfunction "IO,_DIFFIO_R4p,_(CRC_ERROR)_99") (pintype "bidirectional"))
    )
    (net (code "75") (name "/TOF3_INT") (class "Default")
      (node (ref "CN4") (pin "6") (pinfunction "GPIO1_6") (pintype "passive"))
      (node (ref "U4") (pin "75") (pinfunction "IO_75") (pintype "bidirectional"))
    )
    (net (code "76") (name "/TOF3_SCL") (class "Default")
      (node (ref "CN4") (pin "3") (pinfunction "SCL_3") (pintype "passive"))
      (node (ref "U4") (pin "73") (pinfunction "IO_73") (pintype "bidirectional"))
    )
    (net (code "77") (name "/TOF3_SDA") (class "Default")
      (node (ref "CN4") (pin "4") (pinfunction "SDA_4") (pintype "passive"))
      (node (ref "U4") (pin "74") (pinfunction "IO_74") (pintype "bidirectional"))
    )
    (net (code "78") (name "/TOF4_INT") (class "Default")
      (node (ref "CN5") (pin "6") (pinfunction "GPIO1_6") (pintype "passive"))
      (node (ref "U4") (pin "42") (pinfunction "IO,_(DQS1B/CQ1B#,DPCLK2)_42") (pintype "bidirectional"))
    )
    (net (code "79") (name "/TOF4_SCL") (class "Default")
      (node (ref "CN5") (pin "3") (pinfunction "SCL_3") (pintype "passive"))
      (node (ref "U4") (pin "38") (pinfunction "IO,_DIFFIO_B1p_38") (pintype "bidirectional"))
    )
    (net (code "80") (name "/TOF4_SDA") (class "Default")
      (node (ref "CN5") (pin "4") (pinfunction "SDA_4") (pintype "passive"))
      (node (ref "U4") (pin "39") (pinfunction "IO,_DIFFIO_B1n_39") (pintype "bidirectional"))
    )
    (net (code "81") (name "/TOF5_INT") (class "Default")
      (node (ref "CN6") (pin "6") (pinfunction "GPIO1_6") (pintype "passive"))
      (node (ref "U4") (pin "34") (pinfunction "IO_34") (pintype "bidirectional"))
    )
    (net (code "82") (name "/TOF5_SCL") (class "Default")
      (node (ref "CN6") (pin "3") (pinfunction "SCL_3") (pintype "passive"))
      (node (ref "U4") (pin "32") (pinfunction "IO,_RUP1_32") (pintype "bidirectional"))
    )
    (net (code "83") (name "/TOF5_SDA") (class "Default")
      (node (ref "CN6") (pin "4") (pinfunction "SDA_4") (pintype "passive"))
      (node (ref "U4") (pin "33") (pinfunction "IO,_RDN1_33") (pintype "bidirectional"))
    )
    (net (code "84") (name "/TOF6_INT") (class "Default")
      (node (ref "CN8") (pin "6") (pinfunction "GPIO1_6") (pintype "passive"))
      (node (ref "U4") (pin "144") (pinfunction "IO,_DIFFIO_T1p,_(DM1T)_144") (pintype "bidirectional"))
    )
    (net (code "85") (name "/TOF6_SCL") (class "Default")
      (node (ref "CN8") (pin "3") (pinfunction "SCL_3") (pintype "passive"))
      (node (ref "U4") (pin "142") (pinfunction "IO,_DIFFIO_T2p,_(DQS1T/CQ1T#,DPCLK7)_142") (pintype "bidirectional"))
    )
    (net (code "86") (name "/TOF6_SDA") (class "Default")
      (node (ref "CN8") (pin "4") (pinfunction "SDA_4") (pintype "passive"))
      (node (ref "U4") (pin "143") (pinfunction "IO,_DIFFIO_T1n,_(DQ1T)_143") (pintype "bidirectional"))
    )
    (net (code "87") (name "/TOF7_INT") (class "Default")
      (node (ref "CN9") (pin "6") (pinfunction "GPIO1_6") (pintype "passive"))
      (node (ref "U4") (pin "141") (pinfunction "IO,_DIFFIO_T5p_141") (pintype "bidirectional"))
    )
    (net (code "88") (name "/TOF7_SCL") (class "Default")
      (node (ref "CN9") (pin "3") (pinfunction "SCL_3") (pintype "passive"))
      (node (ref "U4") (pin "137") (pinfunction "IO,_(DATA5),_(DQ1T)_137") (pintype "bidirectional"))
    )
    (net (code "89") (name "/TOF7_SDA") (class "Default")
      (node (ref "CN9") (pin "4") (pinfunction "SDA_4") (pintype "passive"))
      (node (ref "U4") (pin "138") (pinfunction "IO,_(DATA6)_138") (pintype "bidirectional"))
    )
    (net (code "90") (name "/TOF8_INT") (class "Default")
      (node (ref "CN7") (pin "6") (pinfunction "GPIO1_6") (pintype "passive"))
      (node (ref "U4") (pin "52") (pinfunction "IO,_DIFFIO_B11p_52") (pintype "bidirectional"))
    )
    (net (code "91") (name "/TOF8_SCL") (class "Default")
      (node (ref "CN7") (pin "3") (pinfunction "SCL_3") (pintype "passive"))
      (node (ref "U4") (pin "50") (pinfunction "IO,_DIFFIO_B9n,_(DQ1B)_50") (pintype "bidirectional"))
    )
    (net (code "92") (name "/TOF8_SDA") (class "Default")
      (node (ref "CN7") (pin "4") (pinfunction "SDA_4") (pintype "passive"))
      (node (ref "U4") (pin "51") (pinfunction "IO,_DIFFIO_B10p,_(DQ1B)_51") (pintype "bidirectional"))
    )
    (net (code "93") (name "/USART1_RX") (class "Default")
      (node (ref "U13") (pin "87") (pinfunction "PD6_87") (pintype "passive"))
      (node (ref "U4") (pin "129") (pinfunction "IO,_DIFFIO_T11p_129") (pintype "bidirectional"))
    )
    (net (code "94") (name "/USART1_TX") (class "Default")
      (node (ref "U13") (pin "86") (pinfunction "PD5_86") (pintype "passive"))
      (node (ref "U4") (pin "128") (pinfunction "IO,_DIFFIO_T11n_128") (pintype "bidirectional"))
    )
    (net (code "95") (name "/USART2_RX") (class "Default")
      (node (ref "CN19") (pin "3") (pinfunction "3_3") (pintype "passive"))
      (node (ref "U13") (pin "56") (pinfunction "PD9_56") (pintype "passive"))
    )
    (net (code "96") (name "/USART2_TX") (class "Default")
      (node (ref "CN19") (pin "4") (pinfunction "4_4") (pintype "passive"))
      (node (ref "U13") (pin "55") (pinfunction "PD8_55") (pintype "passive"))
    )
    (net (code "97") (name "/USB_ENUM") (class "Default")
      (node (ref "R41") (pin "2") (pinfunction "2_2") (pintype "passive"))
      (node (ref "U16") (pin "28") (pinfunction "PB15_28") (pintype "passive"))
    )
    (net (code "98") (name "/USB_N") (class "Default")
      (node (ref "R51") (pin "2") (pinfunction "2_2") (pintype "passive"))
      (node (ref "U16") (pin "32") (pinfunction "PA11_32") (pintype "passive"))
    )
    (net (code "99") (name "/USB_P") (class "Default")
      (node (ref "R50") (pin "2") (pinfunction "2_2") (pintype "passive"))
      (node (ref "U16") (pin "33") (pinfunction "PA12_33") (pintype "passive"))
    )
    (net (code "100") (name "/nCSO") (class "Default")
      (node (ref "U10") (pin "1") (pinfunction "S#_1") (pintype "input"))
      (node (ref "U4") (pin "8") (pinfunction "IO,_DIFFIO_L2p,_(FLASH_nCE,nCSO)_8") (pintype "bidirectional"))
    )
    (net (code "101") (name "1.2V") (class "Default")
      (node (ref "C33") (pin "1") (pinfunction "1_1") (pintype "passive"))
      (node (ref "C34") (pin "1") (pinfunction "1_1") (pintype "passive"))
      (node (ref "C35") (pin "1") (pinfunction "1_1") (pintype "passive"))
      (node (ref "C36") (pin "1") (pinfunction "1_1") (pintype "passive"))
      (node (ref "C37") (pin "1") (pinfunction "1_1") (pintype "passive"))
      (node (ref "C38") (pin "1") (pinfunction "1_1") (pintype "passive"))
      (node (ref "C39") (pin "1") (pinfunction "1_1") (pintype "passive"))
      (node (ref "C4") (pin "1") (pinfunction "1_1") (pintype "passive"))
      (node (ref "C40") (pin "1") (pinfunction "1_1") (pintype "passive"))
      (node (ref "C41") (pin "1") (pinfunction "1_1") (pintype "passive"))
      (node (ref "R16") (pin "2") (pinfunction "2_2") (pintype "passive"))
      (node (ref "U4") (pin "102") (pinfunction "VCCINT_102") (pintype "power_in"))
      (node (ref "U4") (pin "109") (pinfunction "VCCD_PLL2_109") (pintype "power_in"))
      (node (ref "U4") (pin "116") (pinfunction "VCCINT_116") (pintype "power_in"))
      (node (ref "U4") (pin "134") (pinfunction "VCCINT_134") (pintype "power_in"))
      (node (ref "U4") (pin "29") (pinfunction "VCCINT_29") (pintype "power_in"))
      (node (ref "U4") (pin "37") (pinfunction "VCCD_PLL1_37") (pintype "power_in"))
      (node (ref "U4") (pin "45") (pinfunction "VCCINT_45") (pintype "power_in"))
      (node (ref "U4") (pin "5") (pinfunction "VCCINT_5") (pintype "power_in"))
      (node (ref "U4") (pin "61") (pinfunction "VCCINT_61") (pintype "power_in"))
      (node (ref "U4") (pin "78") (pinfunction "VCCINT_78") (pintype "power_in"))
      (node (ref "U5") (pin "2") (pinfunction "OUT_2") (pintype "passive"))
      (node (ref "U5") (pin "4") (pinfunction "=_4") (pintype "passive"))
    )
    (net (code "102") (name "2.5V") (class "Default")
      (node (ref "C15") (pin "1") (pinfunction "1_1") (pintype "passive"))
      (node (ref "C30") (pin "1") (pinfunction "1_1") (pintype "passive"))
      (node (ref "C31") (pin "1") (pinfunction "1_1") (pintype "passive"))
      (node (ref "C32") (pin "1") (pinfunction "1_1") (pintype "passive"))
      (node (ref "R18") (pin "2") (pinfunction "2_2") (pintype "passive"))
      (node (ref "R38") (pin "1") (pinfunction "1_1") (pintype "passive"))
      (node (ref "R39") (pin "1") (pinfunction "1_1") (pintype "passive"))
      (node (ref "U12") (pin "2") (pinfunction "OUT_2") (pintype "passive"))
      (node (ref "U12") (pin "4") (pinfunction "=_4") (pintype "passive"))
      (node (ref "U4") (pin "107") (pinfunction "VCCA2_107") (pintype "power_in"))
      (node (ref "U4") (pin "35") (pinfunction "VCCA1_35") (pintype "power_in"))
      (node (ref "U4") (pin "96") (pinfunction "MSEL1_96") (pintype "input"))
    )
    (net (code "103") (name "3.3V") (class "Default")
      (node (ref "C11") (pin "1") (pinfunction "1_1") (pintype "passive"))
      (node (ref "C16") (pin "1") (pinfunction "1_1") (pintype "passive"))
      (node (ref "C19") (pin "1") (pinfunction "1_1") (pintype "passive"))
      (node (ref "C20") (pin "1") (pinfunction "1_1") (pintype "passive"))
      (node (ref "C21") (pin "1") (pinfunction "1_1") (pintype "passive"))
      (node (ref "C22") (pin "1") (pinfunction "1_1") (pintype "passive"))
      (node (ref "C23") (pin "1") (pinfunction "1_1") (pintype "passive"))
      (node (ref "C24") (pin "1") (pinfunction "1_1") (pintype "passive"))
      (node (ref "C25") (pin "1") (pinfunction "1_1") (pintype "passive"))
      (node (ref "C26") (pin "1") (pinfunction "1_1") (pintype "passive"))
      (node (ref "C27") (pin "1") (pinfunction "1_1") (pintype "passive"))
      (node (ref "C28") (pin "1") (pinfunction "1_1") (pintype "passive"))
      (node (ref "C29") (pin "1") (pinfunction "1_1") (pintype "passive"))
      (node (ref "C9") (pin "1") (pinfunction "1_1") (pintype "passive"))
      (node (ref "CN1") (pin "1") (pinfunction "VIN_1") (pintype "passive"))
      (node (ref "CN2") (pin "1") (pinfunction "VIN_1") (pintype "passive"))
      (node (ref "CN3") (pin "1") (pinfunction "VIN_1") (pintype "passive"))
      (node (ref "CN4") (pin "1") (pinfunction "VIN_1") (pintype "passive"))
      (node (ref "CN5") (pin "1") (pinfunction "VIN_1") (pintype "passive"))
      (node (ref "CN6") (pin "1") (pinfunction "VIN_1") (pintype "passive"))
      (node (ref "CN7") (pin "1") (pinfunction "VIN_1") (pintype "passive"))
      (node (ref "CN8") (pin "1") (pinfunction "VIN_1") (pintype "passive"))
      (node (ref "CN9") (pin "1") (pinfunction "VIN_1") (pintype "passive"))
      (node (ref "R14") (pin "2") (pinfunction "2_2") (pintype "passive"))
      (node (ref "R31") (pin "2") (pinfunction "2_2") (pintype "passive"))
      (node (ref "R32") (pin "2") (pinfunction "2_2") (pintype "passive"))
      (node (ref "R33") (pin "2") (pinfunction "2_2") (pintype "passive"))
      (node (ref "R40") (pin "1") (pinfunction "1_1") (pintype "passive"))
      (node (ref "U10") (pin "3") (pinfunction "W#_3") (pintype "input"))
      (node (ref "U10") (pin "7") (pinfunction "HOLD#_7") (pintype "input"))
      (node (ref "U10") (pin "8") (pinfunction "VCC_8") (pintype "power_in"))
      (node (ref "U4") (pin "117") (pinfunction "VCCIO7_117") (pintype "power_in"))
      (node (ref "U4") (pin "122") (pinfunction "VCCIO7_122") (pintype "power_in"))
      (node (ref "U4") (pin "130") (pinfunction "VCCIO8_130") (pintype "power_in"))
      (node (ref "U4") (pin "139") (pinfunction "VCCIO8_139") (pintype "power_in"))
      (node (ref "U4") (pin "17") (pinfunction "VCCIO1_17") (pintype "power_in"))
      (node (ref "U4") (pin "26") (pinfunction "VCCIO2_26") (pintype "power_in"))
      (node (ref "U4") (pin "40") (pinfunction "VCCIO3_40") (pintype "power_in"))
      (node (ref "U4") (pin "47") (pinfunction "VCCIO3_47") (pintype "power_in"))
      (node (ref "U4") (pin "56") (pinfunction "VCCIO4_56") (pintype "power_in"))
      (node (ref "U4") (pin "62") (pinfunction "VCCIO4_62") (pintype "power_in"))
      (node (ref "U4") (pin "81") (pinfunction "VCCIO5_81") (pintype "power_in"))
      (node (ref "U4") (pin "93") (pinfunction "VCCIO6_93") (pintype "power_in"))
      (node (ref "U8") (pin "2") (pinfunction "OUT_2") (pintype "passive"))
      (node (ref "U8") (pin "4") (pinfunction "=_4") (pintype "passive"))
      (node (ref "X1") (pin "4") (pinfunction "VCC_4") (pintype "passive"))
    )
    (net (code "104") (name "5V") (class "Default")
      (node (ref "C12") (pin "2") (pinfunction "2_2") (pintype "passive"))
      (node (ref "C18") (pin "2") (pinfunction "2_2") (pintype "passive"))
      (node (ref "C2") (pin "1") (pinfunction "1_1") (pintype "passive"))
      (node (ref "C5") (pin "2") (pinfunction "2_2") (pintype "passive"))
      (node (ref "C8") (pin "2") (pinfunction "2_2") (pintype "passive"))
      (node (ref "CN13") (pin "5") (pinfunction "encoder5V_5") (pintype "passive"))
      (node (ref "CN14") (pin "1") (pinfunction "VIN_1") (pintype "passive"))
      (node (ref "CN15") (pin "5") (pinfunction "encoder5V_5") (pintype "passive"))
      (node (ref "CN16") (pin "1") (pinfunction "1_1") (pintype "passive"))
      (node (ref "CN19") (pin "1") (pinfunction "1_1") (pintype "passive"))
      (node (ref "L1") (pin "1") (pinfunction "1_1") (pintype "passive"))
      (node (ref "R7") (pin "2") (pinfunction "2_2") (pintype "passive"))
      (node (ref "R9") (pin "2") (pinfunction "2_2") (pintype "passive"))
      (node (ref "U12") (pin "3") (pinfunction "IN_3") (pintype "passive"))
      (node (ref "U5") (pin "3") (pinfunction "IN_3") (pintype "passive"))
      (node (ref "U6") (pin "3") (pinfunction "IN_3") (pintype "passive"))
      (node (ref "U8") (pin "3") (pinfunction "IN_3") (pintype "passive"))
    )
    (net (code "105") (name "BAT+") (class "Default")
      (node (ref "C3") (pin "1") (pinfunction "1_1") (pintype "passive"))
      (node (ref "CN10") (pin "2") (pinfunction "+_2") (pintype "passive"))
      (node (ref "CN10") (pin "3") (pinfunction "3_3") (pintype "passive"))
      (node (ref "CN11") (pin "4") (pinfunction "4_4") (pintype "passive"))
      (node (ref "CN12") (pin "4") (pinfunction "4_4") (pintype "passive"))
      (node (ref "D1") (pin "1") (pinfunction "K_1") (pintype "passive"))
      (node (ref "D10") (pin "2") (pinfunction "A_2") (pintype "passive"))
      (node (ref "D3") (pin "2") (pinfunction "A_2") (pintype "passive"))
      (node (ref "D6") (pin "2") (pinfunction "A_2") (pintype "passive"))
      (node (ref "D8") (pin "2") (pinfunction "A_2") (pintype "passive"))
      (node (ref "Q1") (pin "2") (pinfunction "D_2") (pintype "passive"))
      (node (ref "Q2") (pin "2") (pinfunction "D_2") (pintype "passive"))
      (node (ref "Q6") (pin "2") (pinfunction "D_2") (pintype "passive"))
      (node (ref "Q7") (pin "2") (pinfunction "D_2") (pintype "passive"))
      (node (ref "R2") (pin "2") (pinfunction "2_2") (pintype "passive"))
      (node (ref "U11") (pin "12") (pinfunction "Vdd_12") (pintype "passive"))
      (node (ref "U11") (pin "2") (pinfunction "BHI_2") (pintype "passive"))
      (node (ref "U11") (pin "7") (pinfunction "AHI_7") (pintype "passive"))
      (node (ref "U2") (pin "7") (pinfunction "VIN_7") (pintype "passive"))
      (node (ref "U7") (pin "12") (pinfunction "Vdd_12") (pintype "passive"))
      (node (ref "U7") (pin "2") (pinfunction "BHI_2") (pintype "passive"))
      (node (ref "U7") (pin "7") (pinfunction "AHI_7") (pintype "passive"))
    )
    (net (code "106") (name "BAT-") (class "Default")
      (node (ref "C13") (pin "1") (pinfunction "1_1") (pintype "passive"))
      (node (ref "CN10") (pin "1") (pinfunction "-_1") (pintype "passive"))
      (node (ref "CN10") (pin "4") (pinfunction "4_4") (pintype "passive"))
      (node (ref "CN11") (pin "1") (pinfunction "1_1") (pintype "passive"))
      (node (ref "CN12") (pin "1") (pinfunction "1_1") (pintype "passive"))
      (node (ref "D1") (pin "2") (pinfunction "A_2") (pintype "passive"))
      (node (ref "K1") (pin "1") (pinfunction "COMMON2_1") (pintype "passive"))
      (node (ref "Q5") (pin "3") (pinfunction "S_3") (pintype "passive"))
      (node (ref "R28") (pin "2") (pinfunction "2_2") (pintype "passive"))
      (node (ref "U9") (pin "2") (pinfunction "GND_2") (pintype "passive"))
    )
    (net (code "107") (name "BAT1+") (class "Default")
      (node (ref "C13") (pin "2") (pinfunction "2_2") (pintype "passive"))
      (node (ref "CN11") (pin "2") (pinfunction "2_2") (pintype "passive"))
      (node (ref "CN12") (pin "2") (pinfunction "2_2") (pintype "passive"))
      (node (ref "R19") (pin "1") (pinfunction "1_1") (pintype "passive"))
      (node (ref "R23") (pin "2") (pinfunction "2_2") (pintype "passive"))
      (node (ref "R4") (pin "2") (pinfunction "2_2") (pintype "passive"))
      (node (ref "U9") (pin "5") (pinfunction "VDD_5") (pintype "passive"))
    )
    (net (code "108") (name "BAT2+") (class "Default")
      (node (ref "CN11") (pin "3") (pinfunction "3_3") (pintype "passive"))
      (node (ref "CN12") (pin "3") (pinfunction "3_3") (pintype "passive"))
      (node (ref "R6") (pin "2") (pinfunction "2_2") (pintype "passive"))
    )
    (net (code "109") (name "GD3.3V") (class "Default")
      (node (ref "C55") (pin "2") (pinfunction "2_2") (pintype "passive"))
      (node (ref "C56") (pin "2") (pinfunction "2_2") (pintype "passive"))
      (node (ref "C57") (pin "2") (pinfunction "2_2") (pintype "passive"))
      (node (ref "C58") (pin "2") (pinfunction "2_2") (pintype "passive"))
      (node (ref "C59") (pin "2") (pinfunction "2_2") (pintype "passive"))
      (node (ref "C6") (pin "1") (pinfunction "1_1") (pintype "passive"))
      (node (ref "C60") (pin "2") (pinfunction "2_2") (pintype "passive"))
      (node (ref "C61") (pin "2") (pinfunction "2_2") (pintype "passive"))
      (node (ref "CN18") (pin "2") (pinfunction "2_2") (pintype "passive"))
      (node (ref "D11") (pin "1") (pinfunction "A_1") (pintype "passive"))
      (node (ref "D11") (pin "2") (pinfunction "A_2") (pintype "passive"))
      (node (ref "D11") (pin "3") (pinfunction "A_3") (pintype "passive"))
      (node (ref "R11") (pin "2") (pinfunction "2_2") (pintype "passive"))
      (node (ref "R52") (pin "1") (pinfunction "1_1") (pintype "passive"))
      (node (ref "R72") (pin "2") (pinfunction "2_2") (pintype "passive"))
      (node (ref "R76") (pin "2") (pinfunction "2_2") (pintype "passive"))
      (node (ref "U1") (pin "8") (pintype "passive"))
      (node (ref "U13") (pin "100") (pinfunction "VDD_3_100") (pintype "passive"))
      (node (ref "U13") (pin "11") (pinfunction "VDD_5_11") (pintype "passive"))
      (node (ref "U13") (pin "19") (pinfunction "VDD_19") (pintype "passive"))
      (node (ref "U13") (pin "21") (pinfunction "VREF+_21") (pintype "passive"))
      (node (ref "U13") (pin "22") (pinfunction "VDDA_22") (pintype "passive"))
      (node (ref "U13") (pin "28") (pinfunction "VDD_4_28") (pintype "passive"))
      (node (ref "U13") (pin "50") (pinfunction "VDD_1_50") (pintype "passive"))
      (node (ref "U13") (pin "6") (pinfunction "VBAT_6") (pintype "passive"))
      (node (ref "U13") (pin "75") (pinfunction "VDD_2_75") (pintype "passive"))
      (node (ref "U3") (pin "8") (pintype "passive"))
      (node (ref "U6") (pin "2") (pinfunction "OUT_2") (pintype "passive"))
      (node (ref "U6") (pin "4") (pinfunction "=_4") (pintype "passive"))
    )
    (net (code "110") (name "GND") (class "Default")
      (node (ref "C11") (pin "2") (pinfunction "2_2") (pintype "passive"))
      (node (ref "C12") (pin "1") (pinfunction "1_1") (pintype "passive"))
      (node (ref "C15") (pin "2") (pinfunction "2_2") (pintype "passive"))
      (node (ref "C16") (pin "2") (pinfunction "2_2") (pintype "passive"))
      (node (ref "C18") (pin "1") (pinfunction "1_1") (pintype "passive"))
      (node (ref "C19") (pin "2") (pinfunction "2_2") (pintype "passive"))
      (node (ref "C2") (pin "2") (pinfunction "2_2") (pintype "passive"))
      (node (ref "C20") (pin "2") (pinfunction "2_2") (pintype "passive"))
      (node (ref "C21") (pin "2") (pinfunction "2_2") (pintype "passive"))
      (node (ref "C22") (pin "2") (pinfunction "2_2") (pintype "passive"))
      (node (ref "C23") (pin "2") (pinfunction "2_2") (pintype "passive"))
      (node (ref "C24") (pin "2") (pinfunction "2_2") (pintype "passive"))
      (node (ref "C25") (pin "2") (pinfunction "2_2") (pintype "passive"))
      (node (ref "C26") (pin "2") (pinfunction "2_2") (pintype "passive"))
      (node (ref "C27") (pin "2") (pinfunction "2_2") (pintype "passive"))
      (node (ref "C28") (pin "2") (pinfunction "2_2") (pintype "passive"))
      (node (ref "C29") (pin "2") (pinfunction "2_2") (pintype "passive"))
      (node (ref "C3") (pin "2") (pinfunction "2_2") (pintype "passive"))
      (node (ref "C30") (pin "2") (pinfunction "2_2") (pintype "passive"))
      (node (ref "C31") (pin "2") (pinfunction "2_2") (pintype "passive"))
      (node (ref "C32") (pin "2") (pinfunction "2_2") (pintype "passive"))
      (node (ref "C33") (pin "2") (pinfunction "2_2") (pintype "passive"))
      (node (ref "C34") (pin "2") (pinfunction "2_2") (pintype "passive"))
      (node (ref "C35") (pin "2") (pinfunction "2_2") (pintype "passive"))
      (node (ref "C36") (pin "2") (pinfunction "2_2") (pintype "passive"))
      (node (ref "C37") (pin "2") (pinfunction "2_2") (pintype "passive"))
      (node (ref "C38") (pin "2") (pinfunction "2_2") (pintype "passive"))
      (node (ref "C39") (pin "2") (pinfunction "2_2") (pintype "passive"))
      (node (ref "C4") (pin "2") (pinfunction "2_2") (pintype "passive"))
      (node (ref "C40") (pin "2") (pinfunction "2_2") (pintype "passive"))
      (node (ref "C41") (pin "2") (pinfunction "2_2") (pintype "passive"))
      (node (ref "C42") (pin "1") (pinfunction "1_1") (pintype "passive"))
      (node (ref "C43") (pin "1") (pinfunction "1_1") (pintype "passive"))
      (node (ref "C44") (pin "1") (pinfunction "1_1") (pintype "passive"))
      (node (ref "C45") (pin "1") (pinfunction "1_1") (pintype "passive"))
      (node (ref "C46") (pin "1") (pinfunction "1_1") (pintype "passive"))
      (node (ref "C47") (pin "1") (pinfunction "1_1") (pintype "passive"))
      (node (ref "C48") (pin "1") (pinfunction "1_1") (pintype "passive"))
      (node (ref "C49") (pin "1") (pinfunction "1_1") (pintype "passive"))
      (node (ref "C5") (pin "1") (pinfunction "1_1") (pintype "passive"))
      (node (ref "C50") (pin "1") (pinfunction "1_1") (pintype "passive"))
      (node (ref "C51") (pin "2") (pinfunction "2_2") (pintype "passive"))
      (node (ref "C52") (pin "2") (pinfunction "2_2") (pintype "passive"))
      (node (ref "C53") (pin "1") (pinfunction "1_1") (pintype "passive"))
      (node (ref "C54") (pin "1") (pinfunction "1_1") (pintype "passive"))
      (node (ref "C55") (pin "1") (pinfunction "1_1") (pintype "passive"))
      (node (ref "C56") (pin "1") (pinfunction "1_1") (pintype "passive"))
      (node (ref "C57") (pin "1") (pinfunction "1_1") (pintype "passive"))
      (node (ref "C58") (pin "1") (pinfunction "1_1") (pintype "passive"))
      (node (ref "C59") (pin "1") (pinfunction "1_1") (pintype "passive"))
      (node (ref "C6") (pin "2") (pinfunction "2_2") (pintype "passive"))
      (node (ref "C60") (pin "1") (pinfunction "1_1") (pintype "passive"))
      (node (ref "C61") (pin "1") (pinfunction "1_1") (pintype "passive"))
      (node (ref "C62") (pin "1") (pinfunction "1_1") (pintype "passive"))
      (node (ref "C63") (pin "1") (pinfunction "1_1") (pintype "passive"))
      (node (ref "C64") (pin "1") (pinfunction "1_1") (pintype "passive"))
      (node (ref "C65") (pin "1") (pinfunction "1_1") (pintype "passive"))
      (node (ref "C66") (pin "1") (pinfunction "1_1") (pintype "passive"))
      (node (ref "C8") (pin "1") (pinfunction "1_1") (pintype "passive"))
      (node (ref "C9") (pin "2") (pinfunction "2_2") (pintype "passive"))
      (node (ref "CN1") (pin "2") (pinfunction "GND_2") (pintype "passive"))
      (node (ref "CN13") (pin "2") (pinfunction "encoderGND_2") (pintype "passive"))
      (node (ref "CN14") (pin "2") (pinfunction "GND_2") (pintype "passive"))
      (node (ref "CN15") (pin "2") (pinfunction "encoderGND_2") (pintype "passive"))
      (node (ref "CN16") (pin "2") (pinfunction "2_2") (pintype "passive"))
      (node (ref "CN17") (pin "15") (pinfunction "EH_15") (pintype "passive"))
      (node (ref "CN17") (pin "A1") (pinfunction "GND_A1") (pintype "passive"))
      (node (ref "CN17") (pin "A12") (pinfunction "GND_A12") (pintype "passive"))
      (node (ref "CN17") (pin "B1") (pinfunction "GND_B1") (pintype "passive"))
      (node (ref "CN17") (pin "B12") (pinfunction "GND_B12") (pintype "passive"))
      (node (ref "CN18") (pin "1") (pinfunction "1_1") (pintype "passive"))
      (node (ref "CN19") (pin "2") (pinfunction "2_2") (pintype "passive"))
      (node (ref "CN2") (pin "2") (pinfunction "GND_2") (pintype "passive"))
      (node (ref "CN20") (pin "15") (pinfunction "EH_15") (pintype "passive"))
      (node (ref "CN20") (pin "A1") (pinfunction "GND_A1") (pintype "passive"))
      (node (ref "CN20") (pin "A12") (pinfunction "GND_A12") (pintype "passive"))
      (node (ref "CN20") (pin "B1") (pinfunction "GND_B1") (pintype "passive"))
      (node (ref "CN20") (pin "B12") (pinfunction "GND_B12") (pintype "passive"))
      (node (ref "CN3") (pin "2") (pinfunction "GND_2") (pintype "passive"))
      (node (ref "CN4") (pin "2") (pinfunction "GND_2") (pintype "passive"))
      (node (ref "CN5") (pin "2") (pinfunction "GND_2") (pintype "passive"))
      (node (ref "CN6") (pin "2") (pinfunction "GND_2") (pintype "passive"))
      (node (ref "CN7") (pin "2") (pinfunction "GND_2") (pintype "passive"))
      (node (ref "CN8") (pin "2") (pinfunction "GND_2") (pintype "passive"))
      (node (ref "CN9") (pin "2") (pinfunction "GND_2") (pintype "passive"))
      (node (ref "D12") (pin "2") (pinfunction "K_2") (pintype "passive"))
      (node (ref "D2") (pin "2") (pinfunction "A_2") (pintype "passive"))
      (node (ref "K2") (pin "1") (pinfunction "COMMON1_1") (pintype "passive"))
      (node (ref "K3") (pin "1") (pinfunction "COMMON1_1") (pintype "passive"))
      (node (ref "K4") (pin "1") (pinfunction "COMMON1_1") (pintype "passive"))
      (node (ref "P1") (pin "1") (pinfunction "1_1") (pintype "passive"))
      (node (ref "P2") (pin "3") (pinfunction "3_3") (pintype "passive"))
      (node (ref "Q3") (pin "3") (pinfunction "S_3") (pintype "passive"))
      (node (ref "Q4") (pin "3") (pinfunction "S_3") (pintype "passive"))
      (node (ref "Q5") (pin "2") (pinfunction "D_2") (pintype "passive"))
      (node (ref "Q8") (pin "3") (pinfunction "S_3") (pintype "passive"))
      (node (ref "Q9") (pin "3") (pinfunction "S_3") (pintype "passive"))
      (node (ref "R1") (pin "1") (pinfunction "1_1") (pintype "passive"))
      (node (ref "R10") (pin "1") (pinfunction "1_1") (pintype "passive"))
      (node (ref "R12") (pin "1") (pinfunction "1_1") (pintype "passive"))
      (node (ref "R13") (pin "1") (pinfunction "1_1") (pintype "passive"))
      (node (ref "R15") (pin "1") (pinfunction "1_1") (pintype "passive"))
      (node (ref "R17") (pin "1") (pinfunction "1_1") (pintype "passive"))
      (node (ref "R27") (pin "1") (pinfunction "1_1") (pintype "passive"))
      (node (ref "R3") (pin "1") (pinfunction "1_1") (pintype "passive"))
      (node (ref "R36") (pin "1") (pinfunction "1_1") (pintype "passive"))
      (node (ref "R37") (pin "1") (pinfunction "1_1") (pintype "passive"))
      (node (ref "R45") (pin "2") (pinfunction "2_2") (pintype "passive"))
      (node (ref "R47") (pin "1") (pinfunction "1_1") (pintype "passive"))
      (node (ref "R5") (pin "1") (pinfunction "1_1") (pintype "passive"))
      (node (ref "R54") (pin "2") (pinfunction "2_2") (pintype "passive"))
      (node (ref "R56") (pin "1") (pinfunction "1_1") (pintype "passive"))
      (node (ref "R57") (pin "1") (pinfunction "1_1") (pintype "passive"))
      (node (ref "R68") (pin "1") (pinfunction "1_1") (pintype "passive"))
      (node (ref "R69") (pin "1") (pinfunction "1_1") (pintype "passive"))
      (node (ref "R70") (pin "1") (pinfunction "1_1") (pintype "passive"))
      (node (ref "R71") (pin "1") (pinfunction "1_1") (pintype "passive"))
      (node (ref "R75") (pin "2") (pinfunction "2_2") (pintype "passive"))
      (node (ref "R78") (pin "1") (pinfunction "1_1") (pintype "passive"))
      (node (ref "R79") (pin "1") (pinfunction "1_1") (pintype "passive"))
      (node (ref "R8") (pin "1") (pinfunction "1_1") (pintype "passive"))
      (node (ref "T1") (pin "2") (pinfunction "E_2") (pintype "passive"))
      (node (ref "T3") (pin "2") (pinfunction "E_2") (pintype "passive"))
      (node (ref "U1") (pin "4") (pintype "passive"))
      (node (ref "U10") (pin "4") (pinfunction "VSS_4") (pintype "power_in"))
      (node (ref "U11") (pin "6") (pinfunction "Vss_6") (pintype "passive"))
      (node (ref "U11") (pin "8") (pinfunction "DIS_8") (pintype "passive"))
      (node (ref "U12") (pin "1") (pinfunction "GND_1") (pintype "passive"))
      (node (ref "U13") (pin "10") (pinfunction "VSS_5_10") (pintype "passive"))
      (node (ref "U13") (pin "20") (pinfunction "VSSA_20") (pintype "passive"))
      (node (ref "U13") (pin "27") (pinfunction "VSS_4_27") (pintype "passive"))
      (node (ref "U13") (pin "74") (pinfunction "VSS_2_74") (pintype "passive"))
      (node (ref "U13") (pin "99") (pinfunction "VSS_3_99") (pintype "passive"))
      (node (ref "U14") (pin "2") (pinfunction "VSS_2") (pintype "passive"))
      (node (ref "U15") (pin "20") (pinfunction "VSS_20") (pintype "passive"))
      (node (ref "U16") (pin "23") (pinfunction "VSS_1_23") (pintype "passive"))
      (node (ref "U16") (pin "35") (pinfunction "VSS_2_35") (pintype "passive"))
      (node (ref "U16") (pin "47") (pinfunction "VSS_3_47") (pintype "passive"))
      (node (ref "U16") (pin "8") (pinfunction "VSSA_8") (pintype "passive"))
      (node (ref "U2") (pin "6") (pinfunction "GND_6") (pintype "passive"))
      (node (ref "U2") (pin "9") (pinfunction "PowerPAD_9") (pintype "passive"))
      (node (ref "U3") (pin "4") (pintype "passive"))
      (node (ref "U4") (pin "108") (pinfunction "GNDA2_108") (pintype "power_in"))
      (node (ref "U4") (pin "118") (pinfunction "GND_118") (pintype "power_in"))
      (node (ref "U4") (pin "123") (pinfunction "GND_123") (pintype "power_in"))
      (node (ref "U4") (pin "131") (pinfunction "GND_131") (pintype "power_in"))
      (node (ref "U4") (pin "140") (pinfunction "GND_140") (pintype "power_in"))
      (node (ref "U4") (pin "145") (pinfunction "GND_145") (pintype "passive"))
      (node (ref "U4") (pin "19") (pinfunction "GND_19") (pintype "power_in"))
      (node (ref "U4") (pin "21") (pinfunction "nCE_21") (pintype "input"))
      (node (ref "U4") (pin "22") (pinfunction "GND_22") (pintype "power_in"))
      (node (ref "U4") (pin "27") (pinfunction "GND_27") (pintype "power_in"))
      (node (ref "U4") (pin "36") (pinfunction "GNDA1_36") (pintype "power_in"))
      (node (ref "U4") (pin "4") (pinfunction "GND_4") (pintype "power_in"))
      (node (ref "U4") (pin "41") (pinfunction "GND_41") (pintype "power_in"))
      (node (ref "U4") (pin "48") (pinfunction "GND_48") (pintype "power_in"))
      (node (ref "U4") (pin "57") (pinfunction "GND_57") (pintype "power_in"))
      (node (ref "U4") (pin "63") (pinfunction "GND_63") (pintype "power_in"))
      (node (ref "U4") (pin "79") (pinfunction "GND_79") (pintype "power_in"))
      (node (ref "U4") (pin "82") (pinfunction "GND_82") (pintype "power_in"))
      (node (ref "U4") (pin "94") (pinfunction "MSEL0_94") (pintype "input"))
      (node (ref "U4") (pin "95") (pinfunction "GND_95") (pintype "power_in"))
      (node (ref "U4") (pin "97") (pinfunction "MSEL2_97") (pintype "input"))
      (node (ref "U5") (pin "1") (pinfunction "GND_1") (pintype "passive"))
      (node (ref "U6") (pin "1") (pinfunction "GND_1") (pintype "passive"))
      (node (ref "U7") (pin "6") (pinfunction "Vss_6") (pintype "passive"))
      (node (ref "U7") (pin "8") (pinfunction "DIS_8") (pintype "passive"))
      (node (ref "U8") (pin "1") (pinfunction "GND_1") (pintype "passive"))
      (node (ref "X1") (pin "2") (pinfunction "GND_2") (pintype "passive"))
    )
    (net (code "111") (name "Net-(B1-+)") (class "Default")
      (node (ref "B1") (pin "1") (pinfunction "+_1") (pintype "passive"))
      (node (ref "D13") (pin "2") (pinfunction "K_2") (pintype "passive"))
      (node (ref "R52") (pin "2") (pinfunction "2_2") (pintype "passive"))
    )
    (net (code "112") (name "Net-(B1--)") (class "Default")
      (node (ref "B1") (pin "2") (pinfunction "-_2") (pintype "passive"))
      (node (ref "D13") (pin "1") (pintype "passive"))
      (node (ref "T3") (pin "3") (pinfunction "C_3") (pintype "passive"))
    )
    (net (code "113") (name "Net-(CN17-DN1)") (class "Default")
      (node (ref "CN17") (pin "A7") (pinfunction "DN1_A7") (pintype "passive"))
      (node (ref "CN17") (pin "B7") (pinfunction "DN2_B7") (pintype "passive"))
      (node (ref "R51") (pin "1") (pinfunction "1_1") (pintype "passive"))
    )
    (net (code "114") (name "Net-(CN17-DP1)") (class "Default")
      (node (ref "CN17") (pin "A6") (pinfunction "DP1_A6") (pintype "passive"))
      (node (ref "CN17") (pin "B6") (pinfunction "DP2_B6") (pintype "passive"))
      (node (ref "R48") (pin "2") (pinfunction "2_2") (pintype "passive"))
      (node (ref "R50") (pin "1") (pinfunction "1_1") (pintype "passive"))
    )
    (net (code "115") (name "Net-(D2-K)") (class "Default")
      (node (ref "C1") (pin "1") (pinfunction "1_1") (pintype "passive"))
      (node (ref "D2") (pin "1") (pinfunction "K_1") (pintype "passive"))
      (node (ref "L1") (pin "2") (pinfunction "2_2") (pintype "passive"))
      (node (ref "U2") (pin "8") (pinfunction "PH_8") (pintype "passive"))
    )
    (net (code "116") (name "Net-(D3-K)") (class "Default")
      (node (ref "C7") (pin "1") (pinfunction "1_1") (pintype "passive"))
      (node (ref "D3") (pin "1") (pinfunction "K_1") (pintype "passive"))
      (node (ref "U7") (pin "1") (pinfunction "BHB_1") (pintype "passive"))
    )
    (net (code "117") (name "Net-(D5-A)") (class "Default")
      (node (ref "D5") (pin "2") (pinfunction "A_2") (pintype "passive"))
      (node (ref "D7") (pin "2") (pinfunction "A_2") (pintype "passive"))
      (node (ref "R23") (pin "1") (pinfunction "1_1") (pintype "passive"))
      (node (ref "R26") (pin "1") (pinfunction "1_1") (pintype "passive"))
    )
    (net (code "118") (name "Net-(D5-K)") (class "Default")
      (node (ref "D5") (pin "1") (pinfunction "K_1") (pintype "passive"))
      (node (ref "R19") (pin "2") (pinfunction "2_2") (pintype "passive"))
      (node (ref "T1") (pin "3") (pinfunction "C_3") (pintype "passive"))
    )
    (net (code "119") (name "Net-(D6-K)") (class "Default")
      (node (ref "C10") (pin "1") (pinfunction "1_1") (pintype "passive"))
      (node (ref "D6") (pin "1") (pinfunction "K_1") (pintype "passive"))
      (node (ref "U7") (pin "9") (pinfunction "AHB_9") (pintype "passive"))
    )
    (net (code "120") (name "Net-(D7-K)") (class "Default")
      (node (ref "D7") (pin "1") (pinfunction "K_1") (pintype "passive"))
      (node (ref "U9") (pin "1") (pinfunction "OUT_1") (pintype "passive"))
    )
    (net (code "121") (name "Net-(D8-K)") (class "Default")
      (node (ref "C14") (pin "1") (pinfunction "1_1") (pintype "passive"))
      (node (ref "D8") (pin "1") (pinfunction "K_1") (pintype "passive"))
      (node (ref "U11") (pin "1") (pinfunction "BHB_1") (pintype "passive"))
    )
    (net (code "122") (name "Net-(D10-K)") (class "Default")
      (node (ref "C17") (pin "1") (pinfunction "1_1") (pintype "passive"))
      (node (ref "D10") (pin "1") (pinfunction "K_1") (pintype "passive"))
      (node (ref "U11") (pin "9") (pinfunction "AHB_9") (pintype "passive"))
    )
    (net (code "123") (name "Net-(D11-K-Pad4)") (class "Default")
      (node (ref "D11") (pin "4") (pinfunction "K_4") (pintype "passive"))
      (node (ref "R49") (pin "2") (pinfunction "2_2") (pintype "passive"))
    )
    (net (code "124") (name "Net-(D11-K-Pad5)") (class "Default")
      (node (ref "D11") (pin "5") (pinfunction "K_5") (pintype "passive"))
      (node (ref "R46") (pin "2") (pinfunction "2_2") (pintype "passive"))
    )
    (net (code "125") (name "Net-(D11-K-Pad6)") (class "Default")
      (node (ref "D11") (pin "6") (pinfunction "K_6") (pintype "passive"))
      (node (ref "R43") (pin "2") (pinfunction "2_2") (pintype "passive"))
    )
    (net (code "126") (name "Net-(D12-A)") (class "Default")
      (node (ref "D12") (pin "1") (pinfunction "A_1") (pintype "passive"))
      (node (ref "R44") (pin "2") (pinfunction "2_2") (pintype "passive"))
    )
    (net (code "127") (name "Net-(D14-K)") (class "Default")
      (node (ref "D14") (pin "2") (pinfunction "K_2") (pintype "passive"))
      (node (ref "R56") (pin "2") (pinfunction "2_2") (pintype "passive"))
    )
    (net (code "128") (name "Net-(D15-K)") (class "Default")
      (node (ref "D15") (pin "2") (pinfunction "K_2") (pintype "passive"))
      (node (ref "R57") (pin "2") (pinfunction "2_2") (pintype "passive"))
    )
    (net (code "129") (name "Net-(D16-A)") (class "Default")
      (node (ref "D16") (pin "1") (pinfunction "A_1") (pintype "passive"))
      (node (ref "U15") (pin "10") (pinfunction "RB7/IOCB7/TX/CK_10") (pintype "passive"))
    )
    (net (code "130") (name "Net-(D16-K)") (class "Default")
      (node (ref "D16") (pin "2") (pinfunction "K_2") (pintype "passive"))
      (node (ref "R71") (pin "2") (pinfunction "2_2") (pintype "passive"))
    )
    (net (code "131") (name "Net-(D17-K)") (class "Default")
      (node (ref "D17") (pin "2") (pinfunction "K_2") (pintype "passive"))
      (node (ref "R79") (pin "2") (pinfunction "2_2") (pintype "passive"))
    )
    (net (code "132") (name "Net-(K1-NO1)") (class "Default")
      (node (ref "K1") (pin "2") (pinfunction "NO1_2") (pintype "passive"))
      (node (ref "U9") (pin "3") (pinfunction "KEY_3") (pintype "passive"))
    )
    (net (code "133") (name "Net-(K4-NO1)") (class "Default")
      (node (ref "K4") (pin "2") (pinfunction "NO1_2") (pintype "passive"))
      (node (ref "R72") (pin "1") (pinfunction "1_1") (pintype "passive"))
      (node (ref "R73") (pin "2") (pinfunction "2_2") (pintype "passive"))
    )
    (net (code "134") (name "Net-(Q1-G)") (class "Default")
      (node (ref "Q1") (pin "1") (pinfunction "G_1") (pintype "passive"))
      (node (ref "R21") (pin "2") (pinfunction "2_2") (pintype "passive"))
    )
    (net (code "135") (name "Net-(Q2-G)") (class "Default")
      (node (ref "Q2") (pin "1") (pinfunction "G_1") (pintype "passive"))
      (node (ref "R20") (pin "1") (pinfunction "1_1") (pintype "passive"))
    )
    (net (code "136") (name "Net-(Q3-G)") (class "Default")
      (node (ref "Q3") (pin "1") (pinfunction "G_1") (pintype "passive"))
      (node (ref "R25") (pin "2") (pinfunction "2_2") (pintype "passive"))
    )
    (net (code "137") (name "Net-(Q4-G)") (class "Default")
      (node (ref "Q4") (pin "1") (pinfunction "G_1") (pintype "passive"))
      (node (ref "R24") (pin "1") (pinfunction "1_1") (pintype "passive"))
    )
    (net (code "138") (name "Net-(Q5-G)") (class "Default")
      (node (ref "Q5") (pin "1") (pinfunction "G_1") (pintype "passive"))
      (node (ref "R26") (pin "2") (pinfunction "2_2") (pintype "passive"))
      (node (ref "R28") (pin "1") (pinfunction "1_1") (pintype "passive"))
    )
    (net (code "139") (name "Net-(Q6-G)") (class "Default")
      (node (ref "Q6") (pin "1") (pinfunction "G_1") (pintype "passive"))
      (node (ref "R30") (pin "2") (pinfunction "2_2") (pintype "passive"))
    )
    (net (code "140") (name "Net-(Q7-G)") (class "Default")
      (node (ref "Q7") (pin "1") (pinfunction "G_1") (pintype "passive"))
      (node (ref "R29") (pin "1") (pinfunction "1_1") (pintype "passive"))
    )
    (net (code "141") (name "Net-(Q8-G)") (class "Default")
      (node (ref "Q8") (pin "1") (pinfunction "G_1") (pintype "passive"))
      (node (ref "R35") (pin "2") (pinfunction "2_2") (pintype "passive"))
    )
    (net (code "142") (name "Net-(Q9-G)") (class "Default")
      (node (ref "Q9") (pin "1") (pinfunction "G_1") (pintype "passive"))
      (node (ref "R34") (pin "1") (pinfunction "1_1") (pintype "passive"))
    )
    (net (code "143") (name "Net-(R1-Pad2)") (class "Default")
      (node (ref "R1") (pin "2") (pinfunction "2_2") (pintype "passive"))
      (node (ref "R2") (pin "1") (pinfunction "1_1") (pintype "passive"))
      (node (ref "U3") (pin "3") (pintype "passive"))
    )
    (net (code "144") (name "Net-(R3-Pad2)") (class "Default")
      (node (ref "R3") (pin "2") (pinfunction "2_2") (pintype "passive"))
      (node (ref "R4") (pin "1") (pinfunction "1_1") (pintype "passive"))
      (node (ref "U1") (pin "3") (pintype "passive"))
    )
    (net (code "145") (name "Net-(R5-Pad2)") (class "Default")
      (node (ref "R5") (pin "2") (pinfunction "2_2") (pintype "passive"))
      (node (ref "R6") (pin "1") (pinfunction "1_1") (pintype "passive"))
      (node (ref "U3") (pin "5") (pintype "passive"))
    )
    (net (code "146") (name "Net-(R8-Pad2)") (class "Default")
      (node (ref "R8") (pin "2") (pinfunction "2_2") (pintype "passive"))
      (node (ref "R9") (pin "1") (pinfunction "1_1") (pintype "passive"))
      (node (ref "U1") (pin "5") (pintype "passive"))
    )
    (net (code "147") (name "Net-(T1-B)") (class "Default")
      (node (ref "R22") (pin "2") (pinfunction "2_2") (pintype "passive"))
      (node (ref "T1") (pin "1") (pinfunction "B_1") (pintype "passive"))
    )
    (net (code "148") (name "Net-(T2-B)") (class "Default")
      (node (ref "R41") (pin "1") (pinfunction "1_1") (pintype "passive"))
      (node (ref "R45") (pin "1") (pinfunction "1_1") (pintype "passive"))
      (node (ref "T2") (pin "1") (pinfunction "B_1") (pintype "passive"))
    )
    (net (code "149") (name "Net-(T2-C)") (class "Default")
      (node (ref "R42") (pin "2") (pinfunction "2_2") (pintype "passive"))
      (node (ref "R48") (pin "1") (pinfunction "1_1") (pintype "passive"))
      (node (ref "T2") (pin "3") (pinfunction "C_3") (pintype "passive"))
    )
    (net (code "150") (name "Net-(T3-B)") (class "Default")
      (node (ref "R53") (pin "2") (pinfunction "2_2") (pintype "passive"))
      (node (ref "T3") (pin "1") (pinfunction "B_1") (pintype "passive"))
    )
    (net (code "151") (name "Net-(U2-BOOT)") (class "Default")
      (node (ref "C1") (pin "2") (pinfunction "2_2") (pintype "passive"))
      (node (ref "U2") (pin "1") (pinfunction "BOOT_1") (pintype "passive"))
    )
    (net (code "152") (name "Net-(U2-VSENSE)") (class "Default")
      (node (ref "R12") (pin "2") (pinfunction "2_2") (pintype "passive"))
      (node (ref "R7") (pin "1") (pinfunction "1_1") (pintype "passive"))
      (node (ref "U2") (pin "4") (pinfunction "VSENSE_4") (pintype "passive"))
    )
    (net (code "153") (name "Net-(U4J-CONF_DONE)") (class "Default")
      (node (ref "R33") (pin "1") (pinfunction "1_1") (pintype "passive"))
      (node (ref "U4") (pin "92") (pinfunction "CONF_DONE_92") (pintype "bidirectional"))
    )
    (net (code "154") (name "Net-(U4J-nCONFIG)") (class "Default")
      (node (ref "R32") (pin "1") (pinfunction "1_1") (pintype "passive"))
      (node (ref "U4") (pin "14") (pinfunction "nCONFIG_14") (pintype "passive"))
    )
    (net (code "155") (name "Net-(U4J-nSTATUS)") (class "Default")
      (node (ref "R31") (pin "1") (pinfunction "1_1") (pintype "passive"))
      (node (ref "U4") (pin "9") (pinfunction "nSTATUS_9") (pintype "bidirectional"))
    )
    (net (code "156") (name "Net-(U7-AHO)") (class "Default")
      (node (ref "R21") (pin "1") (pinfunction "1_1") (pintype "passive"))
      (node (ref "U7") (pin "10") (pinfunction "AHO_10") (pintype "passive"))
    )
    (net (code "157") (name "Net-(U7-ALO)") (class "Default")
      (node (ref "R25") (pin "1") (pinfunction "1_1") (pintype "passive"))
      (node (ref "U7") (pin "13") (pinfunction "ALO_13") (pintype "passive"))
    )
    (net (code "158") (name "Net-(U7-BHO)") (class "Default")
      (node (ref "R20") (pin "2") (pinfunction "2_2") (pintype "passive"))
      (node (ref "U7") (pin "16") (pinfunction "BHO_16") (pintype "passive"))
    )
    (net (code "159") (name "Net-(U7-BLO)") (class "Default")
      (node (ref "R24") (pin "2") (pinfunction "2_2") (pintype "passive"))
      (node (ref "U7") (pin "14") (pinfunction "BLO_14") (pintype "passive"))
    )
    (net (code "160") (name "Net-(U7-DEL)") (class "Default")
      (node (ref "R27") (pin "2") (pinfunction "2_2") (pintype "passive"))
      (node (ref "U7") (pin "5") (pinfunction "DEL_5") (pintype "passive"))
    )
    (net (code "161") (name "Net-(U11-AHO)") (class "Default")
      (node (ref "R30") (pin "1") (pinfunction "1_1") (pintype "passive"))
      (node (ref "U11") (pin "10") (pinfunction "AHO_10") (pintype "passive"))
    )
    (net (code "162") (name "Net-(U11-ALO)") (class "Default")
      (node (ref "R35") (pin "1") (pinfunction "1_1") (pintype "passive"))
      (node (ref "U11") (pin "13") (pinfunction "ALO_13") (pintype "passive"))
    )
    (net (code "163") (name "Net-(U11-BHO)") (class "Default")
      (node (ref "R29") (pin "2") (pinfunction "2_2") (pintype "passive"))
      (node (ref "U11") (pin "16") (pinfunction "BHO_16") (pintype "passive"))
    )
    (net (code "164") (name "Net-(U11-BLO)") (class "Default")
      (node (ref "R34") (pin "2") (pinfunction "2_2") (pintype "passive"))
      (node (ref "U11") (pin "14") (pinfunction "BLO_14") (pintype "passive"))
    )
    (net (code "165") (name "Net-(U11-DEL)") (class "Default")
      (node (ref "R36") (pin "2") (pinfunction "2_2") (pintype "passive"))
      (node (ref "U11") (pin "5") (pinfunction "DEL_5") (pintype "passive"))
    )
    (net (code "166") (name "Net-(U13-BOOT0)") (class "Default")
      (node (ref "R47") (pin "2") (pinfunction "2_2") (pintype "passive"))
      (node (ref "U13") (pin "94") (pinfunction "BOOT0_94") (pintype "passive"))
    )
    (net (code "167") (name "Net-(U13-PB2)") (class "Default")
      (node (ref "R75") (pin "1") (pinfunction "1_1") (pintype "passive"))
      (node (ref "U13") (pin "37") (pinfunction "PB2_37") (pintype "passive"))
    )
    (net (code "168") (name "Net-(U15-RA4{slash}AN3{slash}IOCA3{slash}OSC2{slash}CLKOUT)") (class "Default")
      (node (ref "C47") (pin "2") (pinfunction "2_2") (pintype "passive"))
      (node (ref "U15") (pin "3") (pinfunction "RA4/AN3/IOCA3/OSC2/CLKOUT_3") (pintype "passive"))
      (node (ref "Y1") (pin "2") (pinfunction "OSC2_2") (pintype "passive"))
    )
    (net (code "169") (name "Net-(U15-RA5{slash}IOCA5{slash}OSC1{slash}CLKIN)") (class "Default")
      (node (ref "C46") (pin "2") (pinfunction "2_2") (pintype "passive"))
      (node (ref "U15") (pin "2") (pinfunction "RA5/IOCA5/OSC1/CLKIN_2") (pintype "passive"))
      (node (ref "Y1") (pin "1") (pinfunction "OSC1_1") (pintype "passive"))
    )
    (net (code "170") (name "Net-(U15-RB4{slash}AN10{slash}IOCB4{slash}SDI{slash}SDA)") (class "Default")
      (node (ref "R62") (pin "2") (pinfunction "2_2") (pintype "passive"))
      (node (ref "U15") (pin "13") (pinfunction "RB4/AN10/IOCB4/SDI/SDA_13") (pintype "passive"))
    )
    (net (code "171") (name "Net-(U15-RB6{slash}IOCB6{slash}SCK{slash}SCL)") (class "Default")
      (node (ref "R59") (pin "2") (pinfunction "2_2") (pintype "passive"))
      (node (ref "U15") (pin "11") (pinfunction "RB6/IOCB6/SCK/SCL_11") (pintype "passive"))
    )
    (net (code "172") (name "Net-(U15-RC0{slash}AN4{slash}C12IN+{slash}INT0{slash}VREF+)") (class "Default")
      (node (ref "R58") (pin "2") (pinfunction "2_2") (pintype "passive"))
      (node (ref "U15") (pin "16") (pinfunction "RC0/AN4/C12IN+/INT0/VREF+_16") (pintype "passive"))
    )
    (net (code "173") (name "Net-(U15-RC1{slash}AN5{slash}C12IN1-{slash}INT1{slash}VREF-)") (class "Default")
      (node (ref "R60") (pin "2") (pinfunction "2_2") (pintype "passive"))
      (node (ref "U15") (pin "15") (pinfunction "RC1/AN5/C12IN1-/INT1/VREF-_15") (pintype "passive"))
    )
    (net (code "174") (name "Net-(U15-RC4{slash}P1B{slash}C12OUT{slash}SRQ)") (class "Default")
      (node (ref "R61") (pin "1") (pinfunction "1_1") (pintype "passive"))
      (node (ref "U15") (pin "6") (pinfunction "RC4/P1B/C12OUT/SRQ_6") (pintype "passive"))
    )
    (net (code "175") (name "Net-(U15-RC7{slash}AN9{slash}SDO{slash}T1OSCO)") (class "Default")
      (node (ref "R64") (pin "1") (pinfunction "1_1") (pintype "passive"))
      (node (ref "U15") (pin "9") (pinfunction "RC7/AN9/SDO/T1OSCO_9") (pintype "passive"))
    )
    (net (code "176") (name "Net-(U15-VUSB)") (class "Default")
      (node (ref "C45") (pin "2") (pinfunction "2_2") (pintype "passive"))
      (node (ref "U15") (pin "17") (pinfunction "VUSB_17") (pintype "passive"))
    )
    (net (code "177") (name "Net-(U16-BOOT0)") (class "Default")
      (node (ref "R54") (pin "1") (pinfunction "1_1") (pintype "passive"))
      (node (ref "U16") (pin "44") (pinfunction "BOOT0_44") (pintype "passive"))
    )
    (net (code "178") (name "Net-(U16-NRST)") (class "Default")
      (node (ref "C51") (pin "1") (pinfunction "1_1") (pintype "passive"))
      (node (ref "R65") (pin "1") (pinfunction "1_1") (pintype "passive"))
      (node (ref "U16") (pin "7") (pinfunction "NRST_7") (pintype "passive"))
    )
    (net (code "179") (name "Net-(U16-PB0)") (class "Default")
      (node (ref "R80") (pin "2") (pinfunction "2_2") (pintype "passive"))
      (node (ref "U16") (pin "18") (pinfunction "PB0_18") (pintype "passive"))
    )
    (net (code "180") (name "Net-(U16-PB2{slash}BOOT1)") (class "Default")
      (node (ref "R78") (pin "2") (pinfunction "2_2") (pintype "passive"))
      (node (ref "U16") (pin "20") (pinfunction "PB2/BOOT1_20") (pintype "passive"))
    )
    (net (code "181") (name "Net-(U16-PB12)") (class "Default")
      (node (ref "R74") (pin "1") (pinfunction "1_1") (pintype "passive"))
      (node (ref "U16") (pin "25") (pinfunction "PB12_25") (pintype "passive"))
    )
    (net (code "182") (name "PIC5V") (class "Default")
      (node (ref "C49") (pin "2") (pinfunction "2_2") (pintype "passive"))
      (node (ref "CN20") (pin "A4") (pinfunction "VBUS_A4") (pintype "passive"))
      (node (ref "CN20") (pin "A9") (pinfunction "VBUS_A9") (pintype "passive"))
      (node (ref "CN20") (pin "B4") (pinfunction "VBUS_B4") (pintype "passive"))
      (node (ref "CN20") (pin "B9") (pinfunction "VBUS_B9") (pintype "passive"))
      (node (ref "D17") (pin "1") (pinfunction "A_1") (pintype "passive"))
      (node (ref "P2") (pin "2") (pinfunction "2_2") (pintype "passive"))
      (node (ref "R55") (pin "2") (pinfunction "2_2") (pintype "passive"))
      (node (ref "U15") (pin "1") (pinfunction "VDD_1") (pintype "passive"))
    )
    (net (code "183") (name "ST3.3V") (class "Default")
      (node (ref "C42") (pin "2") (pinfunction "2_2") (pintype "passive"))
      (node (ref "C43") (pin "2") (pinfunction "2_2") (pintype "passive"))
      (node (ref "C63") (pin "2") (pinfunction "2_2") (pintype "passive"))
      (node (ref "C64") (pin "2") (pinfunction "2_2") (pintype "passive"))
      (node (ref "C65") (pin "2") (pinfunction "2_2") (pintype "passive"))
      (node (ref "C66") (pin "2") (pinfunction "2_2") (pintype "passive"))
      (node (ref "R42") (pin "1") (pinfunction "1_1") (pintype "passive"))
      (node (ref "R65") (pin "2") (pinfunction "2_2") (pintype "passive"))
      (node (ref "R80") (pin "1") (pinfunction "1_1") (pintype "passive"))
      (node (ref "T2") (pin "2") (pinfunction "E_2") (pintype "passive"))
      (node (ref "U14") (pin "5") (pinfunction "VOUT_5") (pintype "passive"))
      (node (ref "U16") (pin "1") (pinfunction "VBAT_1") (pintype "passive"))
      (node (ref "U16") (pin "24") (pinfunction "VDD_1_24") (pintype "passive"))
      (node (ref "U16") (pin "36") (pinfunction "VDD_2_36") (pintype "passive"))
      (node (ref "U16") (pin "48") (pinfunction "VDD_3_48") (pintype "passive"))
      (node (ref "U16") (pin "9") (pinfunction "VDDA_9") (pintype "passive"))
    )
    (net (code "184") (name "ST5V") (class "Default")
      (node (ref "C44") (pin "2") (pinfunction "2_2") (pintype "passive"))
      (node (ref "CN17") (pin "A4") (pinfunction "VBUS_A4") (pintype "passive"))
      (node (ref "CN17") (pin "A9") (pinfunction "VBUS_A9") (pintype "passive"))
      (node (ref "CN17") (pin "B4") (pinfunction "VBUS_B4") (pintype "passive"))
      (node (ref "CN17") (pin "B9") (pinfunction "VBUS_B9") (pintype "passive"))
      (node (ref "P1") (pin "4") (pinfunction "4_4") (pintype "passive"))
      (node (ref "U14") (pin "1") (pinfunction "VIN_1") (pintype "passive"))
      (node (ref "U14") (pin "3") (pinfunction "CE_3") (pintype "passive"))
    )
    (net (code "185") (name "unconnected-(CN1-XSHUT-Pad5)") (class "Default")
      (node (ref "CN1") (pin "5") (pinfunction "XSHUT_5") (pintype "passive"))
    )
    (net (code "186") (name "unconnected-(CN2-XSHUT-Pad5)") (class "Default")
      (node (ref "CN2") (pin "5") (pinfunction "XSHUT_5") (pintype "passive"))
    )
    (net (code "187") (name "unconnected-(CN3-XSHUT-Pad5)") (class "Default")
      (node (ref "CN3") (pin "5") (pinfunction "XSHUT_5") (pintype "passive"))
    )
    (net (code "188") (name "unconnected-(CN4-XSHUT-Pad5)") (class "Default")
      (node (ref "CN4") (pin "5") (pinfunction "XSHUT_5") (pintype "passive"))
    )
    (net (code "189") (name "unconnected-(CN5-XSHUT-Pad5)") (class "Default")
      (node (ref "CN5") (pin "5") (pinfunction "XSHUT_5") (pintype "passive"))
    )
    (net (code "190") (name "unconnected-(CN6-XSHUT-Pad5)") (class "Default")
      (node (ref "CN6") (pin "5") (pinfunction "XSHUT_5") (pintype "passive"))
    )
    (net (code "191") (name "unconnected-(CN7-XSHUT-Pad5)") (class "Default")
      (node (ref "CN7") (pin "5") (pinfunction "XSHUT_5") (pintype "passive"))
    )
    (net (code "192") (name "unconnected-(CN8-XSHUT-Pad5)") (class "Default")
      (node (ref "CN8") (pin "5") (pinfunction "XSHUT_5") (pintype "passive"))
    )
    (net (code "193") (name "unconnected-(CN9-XSHUT-Pad5)") (class "Default")
      (node (ref "CN9") (pin "5") (pinfunction "XSHUT_5") (pintype "passive"))
    )
    (net (code "194") (name "unconnected-(CN14-AD0{slash}SDO-Pad7)") (class "Default")
      (node (ref "CN14") (pin "7") (pinfunction "AD0/SDO_7") (pintype "passive"))
    )
    (net (code "195") (name "unconnected-(CN14-ESC-Pad6)") (class "Default")
      (node (ref "CN14") (pin "6") (pinfunction "ESC_6") (pintype "passive"))
    )
    (net (code "196") (name "unconnected-(CN14-ESD-Pad5)") (class "Default")
      (node (ref "CN14") (pin "5") (pinfunction "ESD_5") (pintype "passive"))
    )
    (net (code "197") (name "unconnected-(CN14-FSYNC-Pad10)") (class "Default")
      (node (ref "CN14") (pin "10") (pinfunction "FSYNC_10") (pintype "passive"))
    )
    (net (code "198") (name "unconnected-(CN14-nCS-Pad9)") (class "Default")
      (node (ref "CN14") (pin "9") (pinfunction "nCS_9") (pintype "passive"))
    )
    (net (code "199") (name "unconnected-(CN17-CC1-PadA5)") (class "Default")
      (node (ref "CN17") (pin "A5") (pinfunction "CC1_A5") (pintype "passive"))
    )
    (net (code "200") (name "unconnected-(CN17-CC2-PadB5)") (class "Default")
      (node (ref "CN17") (pin "B5") (pinfunction "CC2_B5") (pintype "passive"))
    )
    (net (code "201") (name "unconnected-(CN20-CC1-PadA5)") (class "Default")
      (node (ref "CN20") (pin "A5") (pinfunction "CC1_A5") (pintype "passive"))
    )
    (net (code "202") (name "unconnected-(CN20-CC2-PadB5)") (class "Default")
      (node (ref "CN20") (pin "B5") (pinfunction "CC2_B5") (pintype "passive"))
    )
    (net (code "203") (name "unconnected-(P2-Pad6)") (class "Default")
      (node (ref "P2") (pin "6") (pinfunction "6_6") (pintype "passive"))
    )
    (net (code "204") (name "unconnected-(U2-ENA-Pad5)") (class "Default")
      (node (ref "U2") (pin "5") (pinfunction "ENA_5") (pintype "passive"))
    )
    (net (code "205") (name "unconnected-(U2-NC-Pad2)") (class "Default")
      (node (ref "U2") (pin "2") (pinfunction "NC_2") (pintype "passive"))
    )
    (net (code "206") (name "unconnected-(U2-NC-Pad3)") (class "Default")
      (node (ref "U2") (pin "3") (pinfunction "NC_3") (pintype "passive"))
    )
    (net (code "207") (name "unconnected-(U4A-IO,_DIFFIO_L4n-Pad11)") (class "Default")
      (node (ref "U4") (pin "11") (pinfunction "IO,_DIFFIO_L4n_11") (pintype "bidirectional"))
    )
    (net (code "208") (name "unconnected-(U4A-IO,_DIFFIO_L4p,_(DQS0L{slash}CQ1L,DPCLK0)-Pad10)") (class "Default")
      (node (ref "U4") (pin "10") (pinfunction "IO,_DIFFIO_L4p,_(DQS0L/CQ1L,DPCLK0)_10") (pintype "bidirectional"))
    )
    (net (code "209") (name "unconnected-(U4A-IO,_VREFB1N0-Pad7)") (class "Default")
      (node (ref "U4") (pin "7") (pinfunction "IO,_VREFB1N0_7") (pintype "bidirectional"))
    )
    (net (code "210") (name "unconnected-(U4A-IO-Pad1)") (class "Default")
      (node (ref "U4") (pin "1") (pinfunction "IO_1") (pintype "bidirectional"))
    )
    (net (code "211") (name "unconnected-(U4A-IO-Pad2)") (class "Default")
      (node (ref "U4") (pin "2") (pinfunction "IO_2") (pintype "bidirectional"))
    )
    (net (code "212") (name "unconnected-(U4A-IO-Pad3)") (class "Default")
      (node (ref "U4") (pin "3") (pinfunction "IO_3") (pintype "bidirectional"))
    )
    (net (code "213") (name "unconnected-(U4B-IO,_DIFFIO_L6n-Pad28)") (class "Default")
      (node (ref "U4") (pin "28") (pinfunction "IO,_DIFFIO_L6n_28") (pintype "bidirectional"))
    )
    (net (code "214") (name "unconnected-(U4B-IO,_DIFFIO_L8p,_(DQS1L{slash}CQ1L#,DPCLK1)-Pad30)") (class "Default")
      (node (ref "U4") (pin "30") (pinfunction "IO,_DIFFIO_L8p,_(DQS1L/CQ1L#,DPCLK1)_30") (pintype "bidirectional"))
    )
    (net (code "215") (name "unconnected-(U4B-IO,_VREFB2N0-Pad31)") (class "Default")
      (node (ref "U4") (pin "31") (pinfunction "IO,_VREFB2N0_31") (pintype "bidirectional"))
    )
    (net (code "216") (name "unconnected-(U4C-IO,_DIFFIO_B9p,_(DQ1B)-Pad49)") (class "Default")
      (node (ref "U4") (pin "49") (pinfunction "IO,_DIFFIO_B9p,_(DQ1B)_49") (pintype "bidirectional"))
    )
    (net (code "217") (name "unconnected-(U4C-IO,_DIFFIO_B11n-Pad53)") (class "Default")
      (node (ref "U4") (pin "53") (pinfunction "IO,_DIFFIO_B11n_53") (pintype "bidirectional"))
    )
    (net (code "218") (name "unconnected-(U4C-IO,_PLL1_CLKOUTn-Pad44)") (class "Default")
      (node (ref "U4") (pin "44") (pinfunction "IO,_PLL1_CLKOUTn_44") (pintype "bidirectional"))
    )
    (net (code "219") (name "unconnected-(U4C-IO,_PLL1_CLKOUTp-Pad43)") (class "Default")
      (node (ref "U4") (pin "43") (pinfunction "IO,_PLL1_CLKOUTp_43") (pintype "bidirectional"))
    )
    (net (code "220") (name "unconnected-(U4C-IO,_VREFB3N0-Pad46)") (class "Default")
      (node (ref "U4") (pin "46") (pinfunction "IO,_VREFB3N0_46") (pintype "bidirectional"))
    )
    (net (code "221") (name "unconnected-(U4D-IO,_DIFFIO_B12n-Pad55)") (class "Default")
      (node (ref "U4") (pin "55") (pinfunction "IO,_DIFFIO_B12n_55") (pintype "bidirectional"))
    )
    (net (code "222") (name "unconnected-(U4D-IO,_DIFFIO_B12p-Pad54)") (class "Default")
      (node (ref "U4") (pin "54") (pinfunction "IO,_DIFFIO_B12p_54") (pintype "bidirectional"))
    )
    (net (code "223") (name "unconnected-(U4D-IO,_DIFFIO_B15p,_(DQ1B)-Pad58)") (class "Default")
      (node (ref "U4") (pin "58") (pinfunction "IO,_DIFFIO_B15p,_(DQ1B)_58") (pintype "bidirectional"))
    )
    (net (code "224") (name "unconnected-(U4D-IO,_DIFFIO_B16n,_(DQ1B)-Pad60)") (class "Default")
      (node (ref "U4") (pin "60") (pinfunction "IO,_DIFFIO_B16n,_(DQ1B)_60") (pintype "bidirectional"))
    )
    (net (code "225") (name "unconnected-(U4D-IO,_DIFFIO_B16p,_(DQ1B)-Pad59)") (class "Default")
      (node (ref "U4") (pin "59") (pinfunction "IO,_DIFFIO_B16p,_(DQ1B)_59") (pintype "bidirectional"))
    )
    (net (code "226") (name "unconnected-(U4D-IO,_DIFFIO_B20n,_(DQS0B{slash}CQ1B,DPCLK3)-Pad68)") (class "Default")
      (node (ref "U4") (pin "68") (pinfunction "IO,_DIFFIO_B20n,_(DQS0B/CQ1B,DPCLK3)_68") (pintype "bidirectional"))
    )
    (net (code "227") (name "unconnected-(U4D-IO,_DIFFIO_B21n-Pad71)") (class "Default")
      (node (ref "U4") (pin "71") (pinfunction "IO,_DIFFIO_B21n_71") (pintype "bidirectional"))
    )
    (net (code "228") (name "unconnected-(U4D-IO,_DIFFIO_B21p-Pad70)") (class "Default")
      (node (ref "U4") (pin "70") (pinfunction "IO,_DIFFIO_B21p_70") (pintype "bidirectional"))
    )
    (net (code "229") (name "unconnected-(U4D-IO,_RDN2,_(DQ1B)-Pad67)") (class "Default")
      (node (ref "U4") (pin "67") (pinfunction "IO,_RDN2,_(DQ1B)_67") (pintype "bidirectional"))
    )
    (net (code "230") (name "unconnected-(U4D-IO,_RUP2,_(DQ1B)-Pad66)") (class "Default")
      (node (ref "U4") (pin "66") (pinfunction "IO,_RUP2,_(DQ1B)_66") (pintype "bidirectional"))
    )
    (net (code "231") (name "unconnected-(U4D-IO,_VREFB4N0-Pad65)") (class "Default")
      (node (ref "U4") (pin "65") (pinfunction "IO,_VREFB4N0_65") (pintype "bidirectional"))
    )
    (net (code "232") (name "unconnected-(U4D-IO-Pad64)") (class "Default")
      (node (ref "U4") (pin "64") (pinfunction "IO_64") (pintype "bidirectional"))
    )
    (net (code "233") (name "unconnected-(U4D-IO-Pad69)") (class "Default")
      (node (ref "U4") (pin "69") (pinfunction "IO_69") (pintype "bidirectional"))
    )
    (net (code "234") (name "unconnected-(U4E-IO,_DIFFIO_R7n,_(DEV_OE)-Pad86)") (class "Default")
      (node (ref "U4") (pin "86") (pinfunction "IO,_DIFFIO_R7n,_(DEV_OE)_86") (pintype "bidirectional"))
    )
    (net (code "235") (name "unconnected-(U4E-IO,_DIFFIO_R7p,_(DEV_CLRn)-Pad87)") (class "Default")
      (node (ref "U4") (pin "87") (pinfunction "IO,_DIFFIO_R7p,_(DEV_CLRn)_87") (pintype "bidirectional"))
    )
    (net (code "236") (name "unconnected-(U4E-IO,_DIFFIO_R8n-Pad84)") (class "Default")
      (node (ref "U4") (pin "84") (pinfunction "IO,_DIFFIO_R8n_84") (pintype "bidirectional"))
    )
    (net (code "237") (name "unconnected-(U4E-IO,_DIFFIO_R8p,_(DQS1R{slash}CQ1R#,DPCLK4)-Pad85)") (class "Default")
      (node (ref "U4") (pin "85") (pinfunction "IO,_DIFFIO_R8p,_(DQS1R/CQ1R#,DPCLK4)_85") (pintype "bidirectional"))
    )
    (net (code "238") (name "unconnected-(U4E-IO,_RDN3-Pad77)") (class "Default")
      (node (ref "U4") (pin "77") (pinfunction "IO,_RDN3_77") (pintype "bidirectional"))
    )
    (net (code "239") (name "unconnected-(U4E-IO,_RUP3-Pad76)") (class "Default")
      (node (ref "U4") (pin "76") (pinfunction "IO,_RUP3_76") (pintype "bidirectional"))
    )
    (net (code "240") (name "unconnected-(U4E-IO,_VREFB5N0-Pad80)") (class "Default")
      (node (ref "U4") (pin "80") (pinfunction "IO,_VREFB5N0_80") (pintype "bidirectional"))
    )
    (net (code "241") (name "unconnected-(U4E-IO-Pad83)") (class "Default")
      (node (ref "U4") (pin "83") (pinfunction "IO_83") (pintype "bidirectional"))
    )
    (net (code "242") (name "unconnected-(U4G-IO,_DIFFIO_T12p-Pad127)") (class "Default")
      (node (ref "U4") (pin "127") (pinfunction "IO,_DIFFIO_T12p_127") (pintype "bidirectional"))
    )
    (net (code "243") (name "unconnected-(U4G-IO,_DIFFIO_T16n,_(DQ1T)-Pad120)") (class "Default")
      (node (ref "U4") (pin "120") (pinfunction "IO,_DIFFIO_T16n,_(DQ1T)_120") (pintype "bidirectional"))
    )
    (net (code "244") (name "unconnected-(U4G-IO,_PLL2_CLKOUTp-Pad113)") (class "Default")
      (node (ref "U4") (pin "113") (pinfunction "IO,_PLL2_CLKOUTp_113") (pintype "bidirectional"))
    )
    (net (code "245") (name "unconnected-(U4G-IO,_RDN4,_(DQ1T)-Pad115)") (class "Default")
      (node (ref "U4") (pin "115") (pinfunction "IO,_RDN4,_(DQ1T)_115") (pintype "bidirectional"))
    )
    (net (code "246") (name "unconnected-(U4G-IO,_RUP4,_(DQ1T)-Pad114)") (class "Default")
      (node (ref "U4") (pin "114") (pinfunction "IO,_RUP4,_(DQ1T)_114") (pintype "bidirectional"))
    )
    (net (code "247") (name "unconnected-(U4G-IO,_VREFB7N0-Pad119)") (class "Default")
      (node (ref "U4") (pin "119") (pinfunction "IO,_VREFB7N0_119") (pintype "bidirectional"))
    )
    (net (code "248") (name "unconnected-(U4H-IO,_DIFFIO_T8n,_(DQ1T)-Pad135)") (class "Default")
      (node (ref "U4") (pin "135") (pinfunction "IO,_DIFFIO_T8n,_(DQ1T)_135") (pintype "bidirectional"))
    )
    (net (code "249") (name "unconnected-(U4H-IO,_DIFFIO_T10n,_(DATA2),_(DQ1T)-Pad132)") (class "Default")
      (node (ref "U4") (pin "132") (pinfunction "IO,_DIFFIO_T10n,_(DATA2),_(DQ1T)_132") (pintype "bidirectional"))
    )
    (net (code "250") (name "unconnected-(U4H-IO,_DIFFIO_T10p,_(DATA3),_(DQ1T)-Pad133)") (class "Default")
      (node (ref "U4") (pin "133") (pinfunction "IO,_DIFFIO_T10p,_(DATA3),_(DQ1T)_133") (pintype "bidirectional"))
    )
    (net (code "251") (name "unconnected-(U4H-IO,_VREFB8N0-Pad136)") (class "Default")
      (node (ref "U4") (pin "136") (pinfunction "IO,_VREFB8N0_136") (pintype "bidirectional"))
    )
    (net (code "252") (name "unconnected-(U4I-CLK3,_DIFFCLK_1n-Pad25)") (class "Default")
      (node (ref "U4") (pin "25") (pinfunction "CLK3,_DIFFCLK_1n_25") (pintype "passive"))
    )
    (net (code "253") (name "unconnected-(U4I-CLK4,_DIFFCLK_2p-Pad91)") (class "Default")
      (node (ref "U4") (pin "91") (pinfunction "CLK4,_DIFFCLK_2p_91") (pintype "passive"))
    )
    (net (code "254") (name "unconnected-(U4I-CLK5,_DIFFCLK_2n-Pad90)") (class "Default")
      (node (ref "U4") (pin "90") (pinfunction "CLK5,_DIFFCLK_2n_90") (pintype "passive"))
    )
    (net (code "255") (name "unconnected-(U4I-CLK6,_DIFFCLK_3p-Pad89)") (class "Default")
      (node (ref "U4") (pin "89") (pinfunction "CLK6,_DIFFCLK_3p_89") (pintype "passive"))
    )
    (net (code "256") (name "unconnected-(U4I-CLK7,_DIFFCLK_3n-Pad88)") (class "Default")
      (node (ref "U4") (pin "88") (pinfunction "CLK7,_DIFFCLK_3n_88") (pintype "passive"))
    )
    (net (code "257") (name "unconnected-(U9-NC-Pad4)") (class "Default")
      (node (ref "U9") (pin "4") (pinfunction "NC_4") (pintype "passive"))
    )
    (net (code "258") (name "unconnected-(U9-NC-Pad6)") (class "Default")
      (node (ref "U9") (pin "6") (pinfunction "NC_6") (pintype "passive"))
    )
    (net (code "259") (name "unconnected-(U13-NC-Pad49)") (class "Default")
      (node (ref "U13") (pin "49") (pinfunction "NC_49") (pintype "passive"))
    )
    (net (code "260") (name "unconnected-(U13-NC-Pad73)") (class "Default")
      (node (ref "U13") (pin "73") (pinfunction "NC_73") (pintype "passive"))
    )
    (net (code "261") (name "unconnected-(U13-PA3-Pad26)") (class "Default")
      (node (ref "U13") (pin "26") (pinfunction "PA3_26") (pintype "passive"))
    )
    (net (code "262") (name "unconnected-(U13-PA12-Pad71)") (class "Default")
      (node (ref "U13") (pin "71") (pinfunction "PA12_71") (pintype "passive"))
    )
    (net (code "263") (name "unconnected-(U13-PA15-Pad77)") (class "Default")
      (node (ref "U13") (pin "77") (pinfunction "PA15_77") (pintype "passive"))
    )
    (net (code "264") (name "unconnected-(U13-PB0-Pad35)") (class "Default")
      (node (ref "U13") (pin "35") (pinfunction "PB0_35") (pintype "passive"))
    )
    (net (code "265") (name "unconnected-(U13-PB1-Pad36)") (class "Default")
      (node (ref "U13") (pin "36") (pinfunction "PB1_36") (pintype "passive"))
    )
    (net (code "266") (name "unconnected-(U13-PB3-Pad89)") (class "Default")
      (node (ref "U13") (pin "89") (pinfunction "PB3_89") (pintype "passive"))
    )
    (net (code "267") (name "unconnected-(U13-PB4-Pad90)") (class "Default")
      (node (ref "U13") (pin "90") (pinfunction "PB4_90") (pintype "passive"))
    )
    (net (code "268") (name "unconnected-(U13-PB5-Pad91)") (class "Default")
      (node (ref "U13") (pin "91") (pinfunction "PB5_91") (pintype "passive"))
    )
    (net (code "269") (name "unconnected-(U13-PC4-Pad33)") (class "Default")
      (node (ref "U13") (pin "33") (pinfunction "PC4_33") (pintype "passive"))
    )
    (net (code "270") (name "unconnected-(U13-PC5-Pad34)") (class "Default")
      (node (ref "U13") (pin "34") (pinfunction "PC5_34") (pintype "passive"))
    )
    (net (code "271") (name "unconnected-(U13-PC8-Pad65)") (class "Default")
      (node (ref "U13") (pin "65") (pinfunction "PC8_65") (pintype "passive"))
    )
    (net (code "272") (name "unconnected-(U13-PC9-Pad66)") (class "Default")
      (node (ref "U13") (pin "66") (pinfunction "PC9_66") (pintype "passive"))
    )
    (net (code "273") (name "unconnected-(U13-PC10-Pad78)") (class "Default")
      (node (ref "U13") (pin "78") (pinfunction "PC10_78") (pintype "passive"))
    )
    (net (code "274") (name "unconnected-(U13-PC11-Pad79)") (class "Default")
      (node (ref "U13") (pin "79") (pinfunction "PC11_79") (pintype "passive"))
    )
    (net (code "275") (name "unconnected-(U13-PC12-Pad80)") (class "Default")
      (node (ref "U13") (pin "80") (pinfunction "PC12_80") (pintype "passive"))
    )
    (net (code "276") (name "unconnected-(U13-PC13_TAMPER_RTC-Pad7)") (class "Default")
      (node (ref "U13") (pin "7") (pinfunction "PC13_TAMPER_RTC_7") (pintype "passive"))
    )
    (net (code "277") (name "unconnected-(U13-PC14_OSC32_IN-Pad8)") (class "Default")
      (node (ref "U13") (pin "8") (pinfunction "PC14_OSC32_IN_8") (pintype "passive"))
    )
    (net (code "278") (name "unconnected-(U13-PC15_OSC32_OUT-Pad9)") (class "Default")
      (node (ref "U13") (pin "9") (pinfunction "PC15_OSC32_OUT_9") (pintype "passive"))
    )
    (net (code "279") (name "unconnected-(U13-PD0-Pad81)") (class "Default")
      (node (ref "U13") (pin "81") (pinfunction "PD0_81") (pintype "passive"))
    )
    (net (code "280") (name "unconnected-(U13-PD1-Pad82)") (class "Default")
      (node (ref "U13") (pin "82") (pinfunction "PD1_82") (pintype "passive"))
    )
    (net (code "281") (name "unconnected-(U13-PD2-Pad83)") (class "Default")
      (node (ref "U13") (pin "83") (pinfunction "PD2_83") (pintype "passive"))
    )
    (net (code "282") (name "unconnected-(U13-PD3-Pad84)") (class "Default")
      (node (ref "U13") (pin "84") (pinfunction "PD3_84") (pintype "passive"))
    )
    (net (code "283") (name "unconnected-(U13-PD4-Pad85)") (class "Default")
      (node (ref "U13") (pin "85") (pinfunction "PD4_85") (pintype "passive"))
    )
    (net (code "284") (name "unconnected-(U13-PD7-Pad88)") (class "Default")
      (node (ref "U13") (pin "88") (pinfunction "PD7_88") (pintype "passive"))
    )
    (net (code "285") (name "unconnected-(U13-PD10-Pad57)") (class "Default")
      (node (ref "U13") (pin "57") (pinfunction "PD10_57") (pintype "passive"))
    )
    (net (code "286") (name "unconnected-(U13-PD11-Pad58)") (class "Default")
      (node (ref "U13") (pin "58") (pinfunction "PD11_58") (pintype "passive"))
    )
    (net (code "287") (name "unconnected-(U13-PD14-Pad61)") (class "Default")
      (node (ref "U13") (pin "61") (pinfunction "PD14_61") (pintype "passive"))
    )
    (net (code "288") (name "unconnected-(U13-PE1-Pad98)") (class "Default")
      (node (ref "U13") (pin "98") (pinfunction "PE1_98") (pintype "passive"))
    )
    (net (code "289") (name "unconnected-(U13-PE2-Pad1)") (class "Default")
      (node (ref "U13") (pin "1") (pinfunction "PE2_1") (pintype "passive"))
    )
    (net (code "290") (name "unconnected-(U13-PE3-Pad2)") (class "Default")
      (node (ref "U13") (pin "2") (pinfunction "PE3_2") (pintype "passive"))
    )
    (net (code "291") (name "unconnected-(U13-PE4-Pad3)") (class "Default")
      (node (ref "U13") (pin "3") (pinfunction "PE4_3") (pintype "passive"))
    )
    (net (code "292") (name "unconnected-(U13-PE6-Pad5)") (class "Default")
      (node (ref "U13") (pin "5") (pinfunction "PE6_5") (pintype "passive"))
    )
    (net (code "293") (name "unconnected-(U13-PE7-Pad38)") (class "Default")
      (node (ref "U13") (pin "38") (pinfunction "PE7_38") (pintype "passive"))
    )
    (net (code "294") (name "unconnected-(U13-PE8-Pad39)") (class "Default")
      (node (ref "U13") (pin "39") (pinfunction "PE8_39") (pintype "passive"))
    )
    (net (code "295") (name "unconnected-(U13-PE9-Pad40)") (class "Default")
      (node (ref "U13") (pin "40") (pinfunction "PE9_40") (pintype "passive"))
    )
    (net (code "296") (name "unconnected-(U13-PE10-Pad41)") (class "Default")
      (node (ref "U13") (pin "41") (pinfunction "PE10_41") (pintype "passive"))
    )
    (net (code "297") (name "unconnected-(U13-PE11-Pad42)") (class "Default")
      (node (ref "U13") (pin "42") (pinfunction "PE11_42") (pintype "passive"))
    )
    (net (code "298") (name "unconnected-(U13-PE12-Pad43)") (class "Default")
      (node (ref "U13") (pin "43") (pinfunction "PE12_43") (pintype "passive"))
    )
    (net (code "299") (name "unconnected-(U13-PE13-Pad44)") (class "Default")
      (node (ref "U13") (pin "44") (pinfunction "PE13_44") (pintype "passive"))
    )
    (net (code "300") (name "unconnected-(U13-PE14-Pad45)") (class "Default")
      (node (ref "U13") (pin "45") (pinfunction "PE14_45") (pintype "passive"))
    )
    (net (code "301") (name "unconnected-(U14-NC-Pad4)") (class "Default")
      (node (ref "U14") (pin "4") (pinfunction "NC_4") (pintype "passive"))
    )
    (net (code "302") (name "unconnected-(U15-RB5{slash}AN11{slash}IOCB5{slash}RX{slash}DT-Pad12)") (class "Default")
      (node (ref "U15") (pin "12") (pinfunction "RB5/AN11/IOCB5/RX/DT_12") (pintype "passive"))
    )
    (net (code "303") (name "unconnected-(U15-RC2{slash}AN6{slash}P1D{slash}C12IN2-{slash}CVREF{slash}INT2-Pad14)") (class "Default")
      (node (ref "U15") (pin "14") (pinfunction "RC2/AN6/P1D/C12IN2-/CVREF/INT2_14") (pintype "passive"))
    )
    (net (code "304") (name "unconnected-(U15-RC3{slash}AN7{slash}P1C{slash}C12IN3-{slash}PGM-Pad7)") (class "Default")
      (node (ref "U15") (pin "7") (pinfunction "RC3/AN7/P1C/C12IN3-/PGM_7") (pintype "passive"))
    )
    (net (code "305") (name "unconnected-(U15-RC5{slash}CCP1{slash}P1A{slash}T0CKI-Pad5)") (class "Default")
      (node (ref "U15") (pin "5") (pinfunction "RC5/CCP1/P1A/T0CKI_5") (pintype "passive"))
    )
    (net (code "306") (name "unconnected-(U15-RC6{slash}AN8{slash}SS#{slash}T13CKI{slash}T1OSCI-Pad8)") (class "Default")
      (node (ref "U15") (pin "8") (pinfunction "RC6/AN8/SS#/T13CKI/T1OSCI_8") (pintype "passive"))
    )
    (net (code "307") (name "unconnected-(U16-PA0-Pad10)") (class "Default")
      (node (ref "U16") (pin "10") (pinfunction "PA0_10") (pintype "passive"))
    )
    (net (code "308") (name "unconnected-(U16-PA1-Pad11)") (class "Default")
      (node (ref "U16") (pin "11") (pinfunction "PA1_11") (pintype "passive"))
    )
    (net (code "309") (name "unconnected-(U16-PA4-Pad14)") (class "Default")
      (node (ref "U16") (pin "14") (pinfunction "PA4_14") (pintype "passive"))
    )
    (net (code "310") (name "unconnected-(U16-PA5-Pad15)") (class "Default")
      (node (ref "U16") (pin "15") (pinfunction "PA5_15") (pintype "passive"))
    )
    (net (code "311") (name "unconnected-(U16-PA6-Pad16)") (class "Default")
      (node (ref "U16") (pin "16") (pinfunction "PA6_16") (pintype "passive"))
    )
    (net (code "312") (name "unconnected-(U16-PA7-Pad17)") (class "Default")
      (node (ref "U16") (pin "17") (pinfunction "PA7_17") (pintype "passive"))
    )
    (net (code "313") (name "unconnected-(U16-PA8-Pad29)") (class "Default")
      (node (ref "U16") (pin "29") (pinfunction "PA8_29") (pintype "passive"))
    )
    (net (code "314") (name "unconnected-(U16-PA10-Pad31)") (class "Default")
      (node (ref "U16") (pin "31") (pinfunction "PA10_31") (pintype "passive"))
    )
    (net (code "315") (name "unconnected-(U16-PA15-Pad38)") (class "Default")
      (node (ref "U16") (pin "38") (pinfunction "PA15_38") (pintype "passive"))
    )
    (net (code "316") (name "unconnected-(U16-PB1-Pad19)") (class "Default")
      (node (ref "U16") (pin "19") (pinfunction "PB1_19") (pintype "passive"))
    )
    (net (code "317") (name "unconnected-(U16-PB3-Pad39)") (class "Default")
      (node (ref "U16") (pin "39") (pinfunction "PB3_39") (pintype "passive"))
    )
    (net (code "318") (name "unconnected-(U16-PB4-Pad40)") (class "Default")
      (node (ref "U16") (pin "40") (pinfunction "PB4_40") (pintype "passive"))
    )
    (net (code "319") (name "unconnected-(U16-PB5-Pad41)") (class "Default")
      (node (ref "U16") (pin "41") (pinfunction "PB5_41") (pintype "passive"))
    )
    (net (code "320") (name "unconnected-(U16-PB7-Pad43)") (class "Default")
      (node (ref "U16") (pin "43") (pinfunction "PB7_43") (pintype "passive"))
    )
    (net (code "321") (name "unconnected-(U16-PB8-Pad45)") (class "Default")
      (node (ref "U16") (pin "45") (pinfunction "PB8_45") (pintype "passive"))
    )
    (net (code "322") (name "unconnected-(U16-PB9-Pad46)") (class "Default")
      (node (ref "U16") (pin "46") (pinfunction "PB9_46") (pintype "passive"))
    )
    (net (code "323") (name "unconnected-(U16-PB10-Pad21)") (class "Default")
      (node (ref "U16") (pin "21") (pinfunction "PB10_21") (pintype "passive"))
    )
    (net (code "324") (name "unconnected-(U16-PB11-Pad22)") (class "Default")
      (node (ref "U16") (pin "22") (pinfunction "PB11_22") (pintype "passive"))
    )
    (net (code "325") (name "unconnected-(U16-PC13-Pad2)") (class "Default")
      (node (ref "U16") (pin "2") (pinfunction "PC13_2") (pintype "passive"))
    )
    (net (code "326") (name "unconnected-(U16-PC14-Pad3)") (class "Default")
      (node (ref "U16") (pin "3") (pinfunction "PC14_3") (pintype "passive"))
    )
    (net (code "327") (name "unconnected-(U16-PC15-Pad4)") (class "Default")
      (node (ref "U16") (pin "4") (pinfunction "PC15_4") (pintype "passive"))
    )
    (net (code "328") (name "unconnected-(X1-NC-Pad1)") (class "Default")
      (node (ref "X1") (pin "1") (pinfunction "NC_1") (pintype "passive"))
    )
  )
)
